# gator.net
KiCad netlist of a schematic drawn in EAGLE
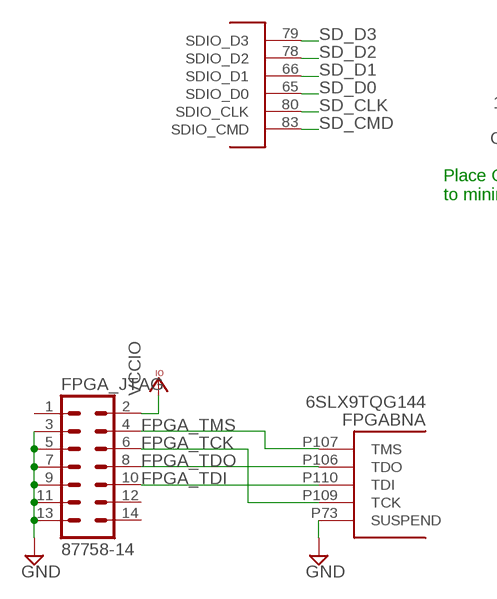
[diagram p0: schematic, sheet 1, part 1 of 2]
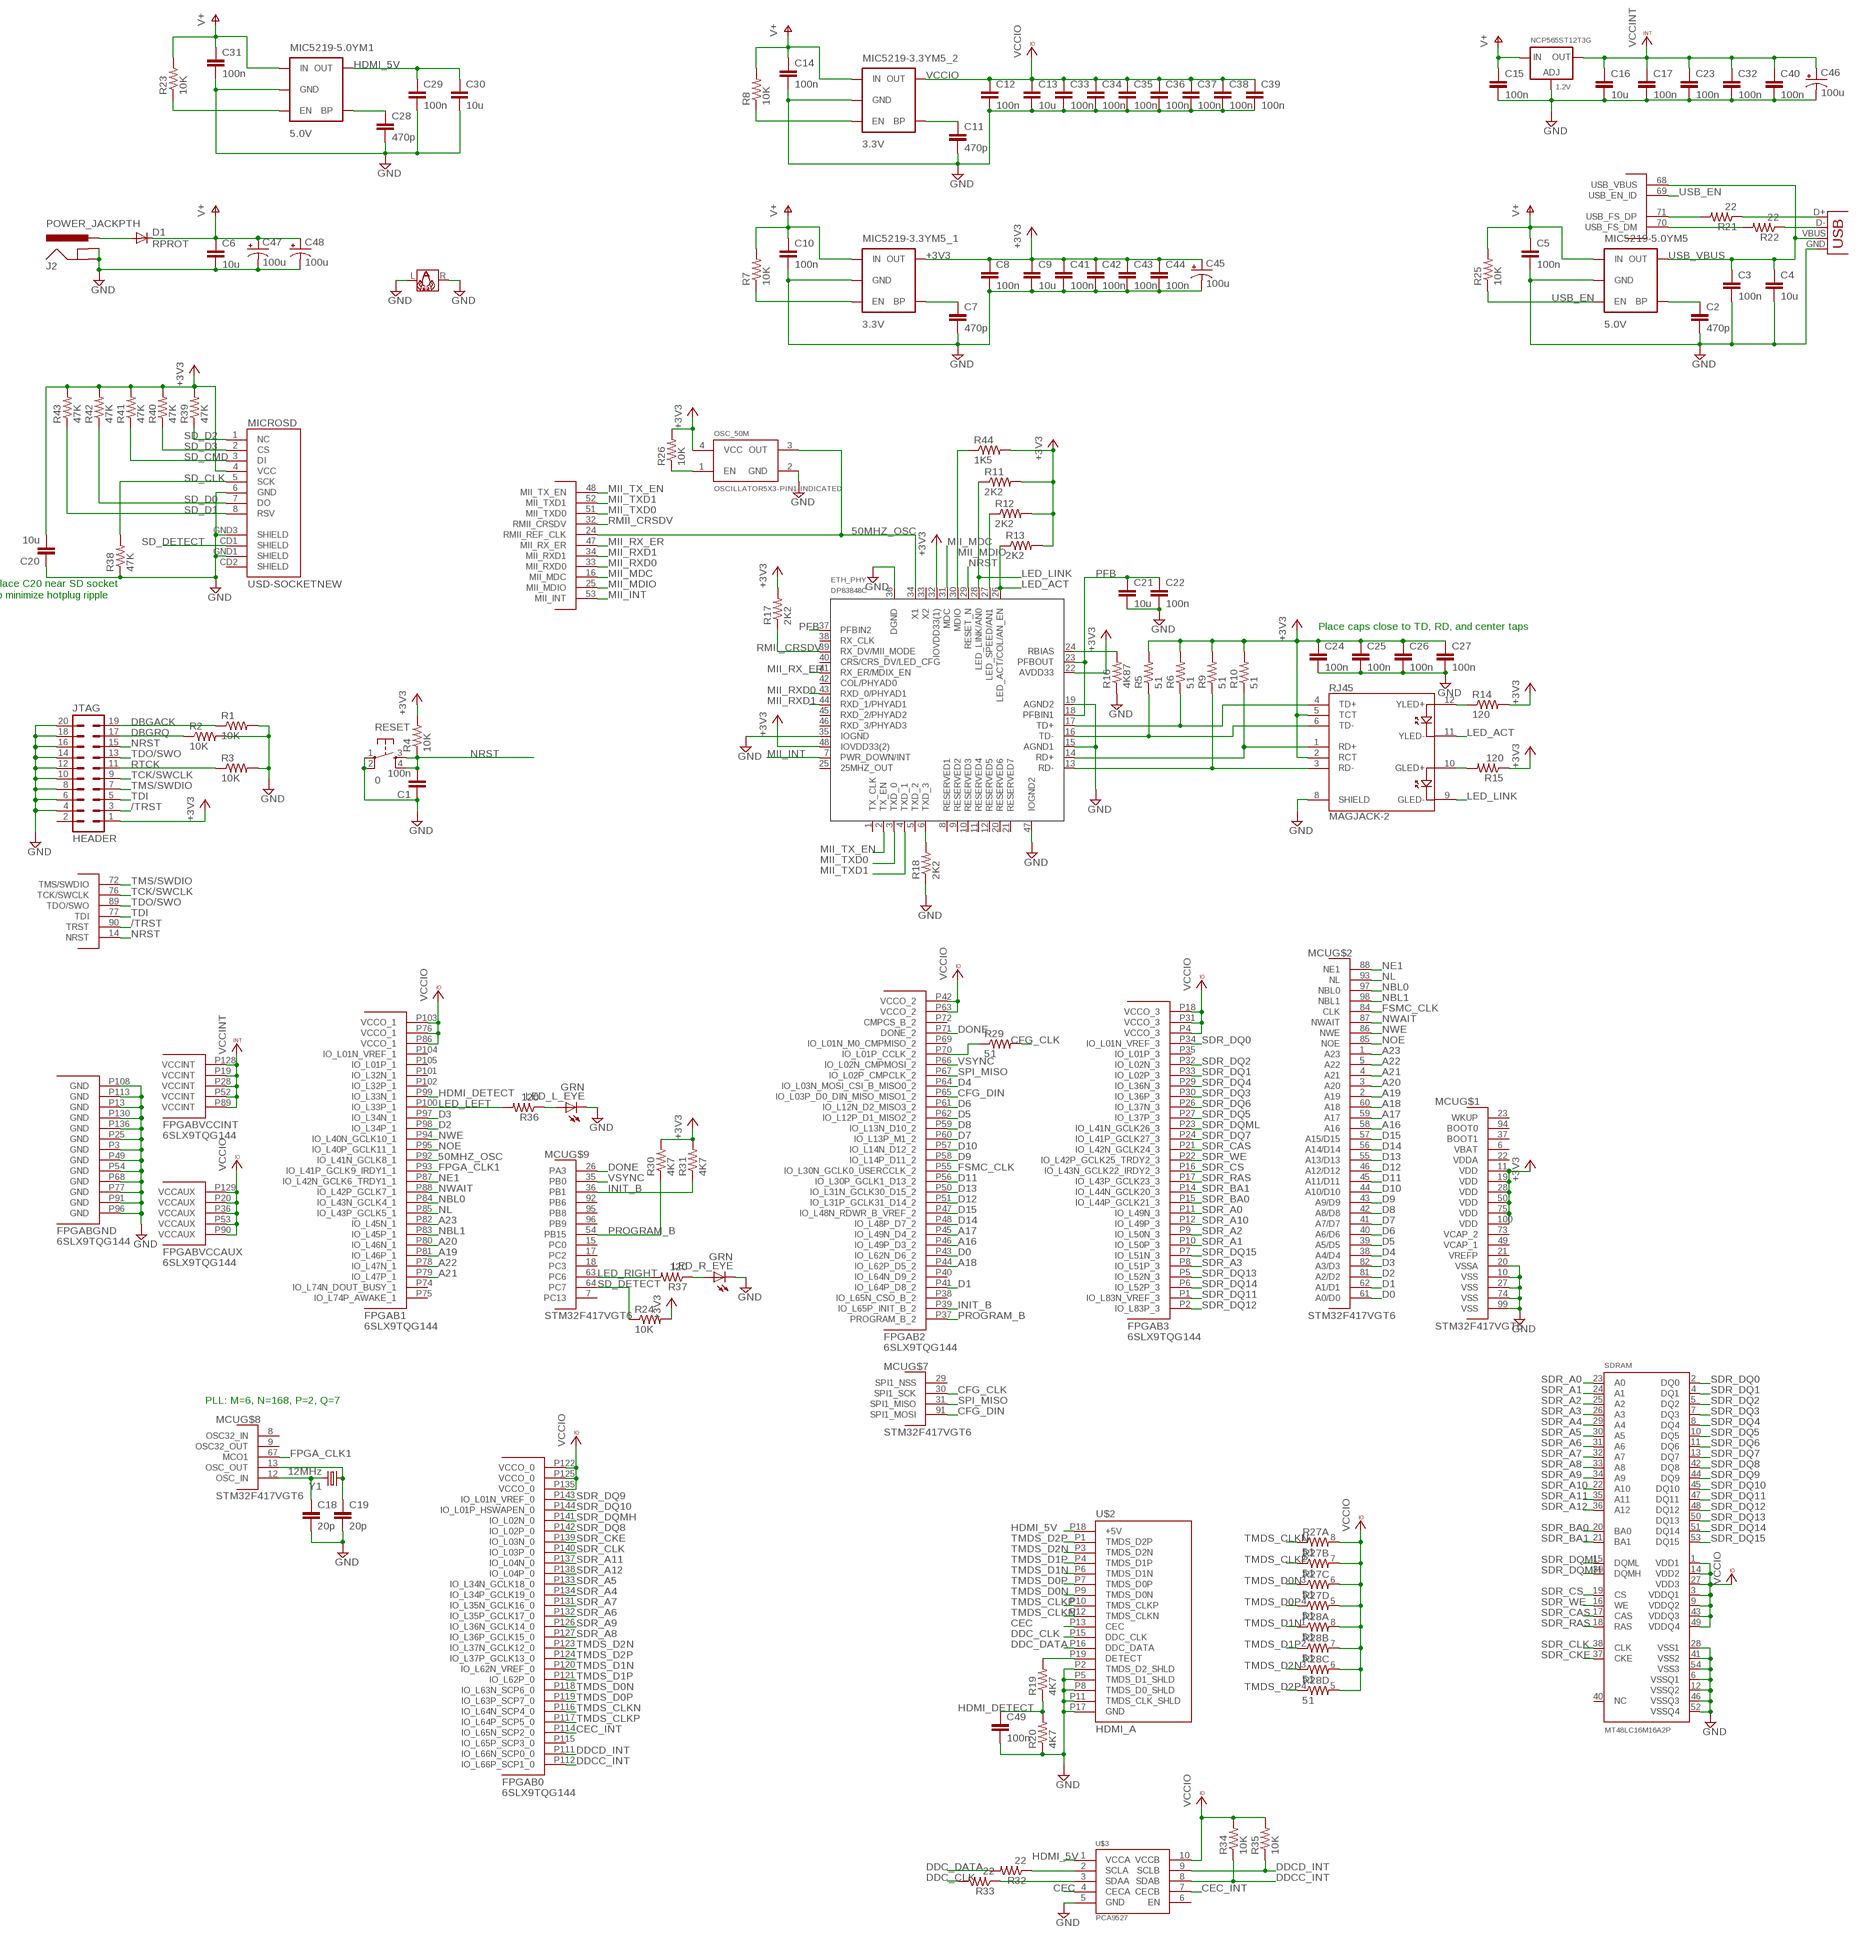
[diagram p1: schematic, sheet 1, part 2 of 2]

(export (version "E")
  (design (tool "Eeschema 10.0.6"))
  (components
    (comp (ref "C1")
      (value "100n")
      (footprint "eagle-import:0603-CAP")
      (fields (field (name "MANF") "TDK Corporation"))
      (libsource (lib "eagle-import") (part "CAP0603-CAP"))
    )
    (comp (ref "C2")
      (value "470p")
      (footprint "eagle-import:0603-CAP")
      (fields (field (name "MANF") "TDK Corporation"))
      (libsource (lib "eagle-import") (part "CAP0603-CAP"))
    )
    (comp (ref "C3")
      (value "100n")
      (footprint "eagle-import:0603-CAP")
      (fields (field (name "MANF") "TDK Corporation"))
      (libsource (lib "eagle-import") (part "CAP0603-CAP"))
    )
    (comp (ref "C4")
      (value "10u")
      (footprint "eagle-import:0603-CAP")
      (fields (field (name "MANF") "TDK Corporation"))
      (libsource (lib "eagle-import") (part "CAP0603-CAP"))
    )
    (comp (ref "C5")
      (value "100n")
      (footprint "eagle-import:0603-CAP")
      (fields (field (name "MANF") "TDK Corporation"))
      (libsource (lib "eagle-import") (part "CAP0603-CAP"))
    )
    (comp (ref "C6")
      (value "10u")
      (footprint "eagle-import:0603-CAP")
      (fields (field (name "MANF") "TDK Corporation"))
      (libsource (lib "eagle-import") (part "CAP0603-CAP"))
    )
    (comp (ref "C7")
      (value "470p")
      (footprint "eagle-import:0603-CAP")
      (fields (field (name "MANF") "TDK Corporation"))
      (libsource (lib "eagle-import") (part "CAP0603-CAP"))
    )
    (comp (ref "C8")
      (value "100n")
      (footprint "eagle-import:0603-CAP")
      (fields (field (name "MANF") "TDK Corporation"))
      (libsource (lib "eagle-import") (part "CAP0603-CAP"))
    )
    (comp (ref "C9")
      (value "10u")
      (footprint "eagle-import:0603-CAP")
      (fields (field (name "MANF") "TDK Corporation"))
      (libsource (lib "eagle-import") (part "CAP0603-CAP"))
    )
    (comp (ref "C10")
      (value "100n")
      (footprint "eagle-import:0603-CAP")
      (fields (field (name "MANF") "TDK Corporation"))
      (libsource (lib "eagle-import") (part "CAP0603-CAP"))
    )
    (comp (ref "C11")
      (value "470p")
      (footprint "eagle-import:0603-CAP")
      (fields (field (name "MANF") "TDK Corporation"))
      (libsource (lib "eagle-import") (part "CAP0603-CAP"))
    )
    (comp (ref "C12")
      (value "100n")
      (footprint "eagle-import:0603-CAP")
      (fields (field (name "MANF") "TDK Corporation"))
      (libsource (lib "eagle-import") (part "CAP0603-CAP"))
    )
    (comp (ref "C13")
      (value "10u")
      (footprint "eagle-import:0603-CAP")
      (fields (field (name "MANF") "TDK Corporation"))
      (libsource (lib "eagle-import") (part "CAP0603-CAP"))
    )
    (comp (ref "C14")
      (value "100n")
      (footprint "eagle-import:0603-CAP")
      (fields (field (name "MANF") "TDK Corporation"))
      (libsource (lib "eagle-import") (part "CAP0603-CAP"))
    )
    (comp (ref "C15")
      (value "100n")
      (footprint "eagle-import:0603-CAP")
      (fields (field (name "MANF") "TDK Corporation"))
      (libsource (lib "eagle-import") (part "CAP0603-CAP"))
    )
    (comp (ref "C16")
      (value "10u")
      (footprint "eagle-import:0603-CAP")
      (fields (field (name "MANF") "TDK Corporation"))
      (libsource (lib "eagle-import") (part "CAP0603-CAP"))
    )
    (comp (ref "C17")
      (value "100n")
      (footprint "eagle-import:0603-CAP")
      (fields (field (name "MANF") "TDK Corporation"))
      (libsource (lib "eagle-import") (part "CAP0603-CAP"))
    )
    (comp (ref "C18")
      (value "20p")
      (footprint "eagle-import:0603-CAP")
      (fields (field (name "MANF") "Murata Electronics North America"))
      (libsource (lib "eagle-import") (part "CAP0603-CAP"))
    )
    (comp (ref "C19")
      (value "20p")
      (footprint "eagle-import:0603-CAP")
      (fields (field (name "MANF") "Murata Electronics North America"))
      (libsource (lib "eagle-import") (part "CAP0603-CAP"))
    )
    (comp (ref "C20")
      (value "10u")
      (footprint "eagle-import:0603-CAP")
      (fields (field (name "MANF") "TDK Corporation"))
      (libsource (lib "eagle-import") (part "CAP0603-CAP"))
    )
    (comp (ref "C21")
      (value "10u")
      (footprint "eagle-import:0603-CAP")
      (fields (field (name "MANF") "TDK Corporation"))
      (libsource (lib "eagle-import") (part "CAP0603-CAP"))
    )
    (comp (ref "C22")
      (value "100n")
      (footprint "eagle-import:0603-CAP")
      (fields (field (name "MANF") "TDK Corporation"))
      (libsource (lib "eagle-import") (part "CAP0603-CAP"))
    )
    (comp (ref "C23")
      (value "100n")
      (footprint "eagle-import:0603-CAP")
      (fields (field (name "MANF") "TDK Corporation"))
      (libsource (lib "eagle-import") (part "CAP0603-CAP"))
    )
    (comp (ref "C24")
      (value "100n")
      (footprint "eagle-import:0603-CAP")
      (fields (field (name "MANF") "TDK Corporation"))
      (libsource (lib "eagle-import") (part "CAP0603-CAP"))
    )
    (comp (ref "C25")
      (value "100n")
      (footprint "eagle-import:0603-CAP")
      (fields (field (name "MANF") "TDK Corporation"))
      (libsource (lib "eagle-import") (part "CAP0603-CAP"))
    )
    (comp (ref "C26")
      (value "100n")
      (footprint "eagle-import:0603-CAP")
      (fields (field (name "MANF") "TDK Corporation"))
      (libsource (lib "eagle-import") (part "CAP0603-CAP"))
    )
    (comp (ref "C27")
      (value "100n")
      (footprint "eagle-import:0603-CAP")
      (fields (field (name "MANF") "TDK Corporation"))
      (libsource (lib "eagle-import") (part "CAP0603-CAP"))
    )
    (comp (ref "C28")
      (value "470p")
      (footprint "eagle-import:0603-CAP")
      (fields (field (name "MANF") "TDK Corporation"))
      (libsource (lib "eagle-import") (part "CAP0603-CAP"))
    )
    (comp (ref "C29")
      (value "100n")
      (footprint "eagle-import:0603-CAP")
      (fields (field (name "MANF") "TDK Corporation"))
      (libsource (lib "eagle-import") (part "CAP0603-CAP"))
    )
    (comp (ref "C30")
      (value "10u")
      (footprint "eagle-import:0603-CAP")
      (fields (field (name "MANF") "TDK Corporation"))
      (libsource (lib "eagle-import") (part "CAP0603-CAP"))
    )
    (comp (ref "C31")
      (value "100n")
      (footprint "eagle-import:0603-CAP")
      (fields (field (name "MANF") "TDK Corporation"))
      (libsource (lib "eagle-import") (part "CAP0603-CAP"))
    )
    (comp (ref "C32")
      (value "100n")
      (footprint "eagle-import:0603-CAP")
      (fields (field (name "MANF") "TDK Corporation"))
      (libsource (lib "eagle-import") (part "CAP0603-CAP"))
    )
    (comp (ref "C33")
      (value "100n")
      (footprint "eagle-import:0603-CAP")
      (fields (field (name "MANF") "TDK Corporation"))
      (libsource (lib "eagle-import") (part "CAP0603-CAP"))
    )
    (comp (ref "C34")
      (value "100n")
      (footprint "eagle-import:0603-CAP")
      (fields (field (name "MANF") "TDK Corporation"))
      (libsource (lib "eagle-import") (part "CAP0603-CAP"))
    )
    (comp (ref "C35")
      (value "100n")
      (footprint "eagle-import:0603-CAP")
      (fields (field (name "MANF") "TDK Corporation"))
      (libsource (lib "eagle-import") (part "CAP0603-CAP"))
    )
    (comp (ref "C36")
      (value "100n")
      (footprint "eagle-import:0603-CAP")
      (fields (field (name "MANF") "TDK Corporation"))
      (libsource (lib "eagle-import") (part "CAP0603-CAP"))
    )
    (comp (ref "C37")
      (value "100n")
      (footprint "eagle-import:0603-CAP")
      (fields (field (name "MANF") "TDK Corporation"))
      (libsource (lib "eagle-import") (part "CAP0603-CAP"))
    )
    (comp (ref "C38")
      (value "100n")
      (footprint "eagle-import:0603-CAP")
      (fields (field (name "MANF") "TDK Corporation"))
      (libsource (lib "eagle-import") (part "CAP0603-CAP"))
    )
    (comp (ref "C39")
      (value "100n")
      (footprint "eagle-import:0603-CAP")
      (fields (field (name "MANF") "TDK Corporation"))
      (libsource (lib "eagle-import") (part "CAP0603-CAP"))
    )
    (comp (ref "C40")
      (value "100n")
      (footprint "eagle-import:0603-CAP")
      (fields (field (name "MANF") "TDK Corporation"))
      (libsource (lib "eagle-import") (part "CAP0603-CAP"))
    )
    (comp (ref "C41")
      (value "100n")
      (footprint "eagle-import:0603-CAP")
      (fields (field (name "MANF") "TDK Corporation"))
      (libsource (lib "eagle-import") (part "CAP0603-CAP"))
    )
    (comp (ref "C42")
      (value "100n")
      (footprint "eagle-import:0603-CAP")
      (fields (field (name "MANF") "TDK Corporation"))
      (libsource (lib "eagle-import") (part "CAP0603-CAP"))
    )
    (comp (ref "C43")
      (value "100n")
      (footprint "eagle-import:0603-CAP")
      (fields (field (name "MANF") "TDK Corporation"))
      (libsource (lib "eagle-import") (part "CAP0603-CAP"))
    )
    (comp (ref "C44")
      (value "100n")
      (footprint "eagle-import:0603-CAP")
      (fields (field (name "MANF") "TDK Corporation"))
      (libsource (lib "eagle-import") (part "CAP0603-CAP"))
    )
    (comp (ref "C45")
      (value "100u")
      (footprint "eagle-import:CPOL-RADIAL-100UF-25V")
      (fields (field (name "MANF") "Rubycon"))
      (libsource (lib "eagle-import") (part "CAP_POLPTH1"))
    )
    (comp (ref "C46")
      (value "100u")
      (footprint "eagle-import:CPOL-RADIAL-100UF-25V")
      (fields (field (name "MANF") "Rubycon"))
      (libsource (lib "eagle-import") (part "CAP_POLPTH1"))
    )
    (comp (ref "C47")
      (value "100u")
      (footprint "eagle-import:CPOL-RADIAL-100UF-25V")
      (fields (field (name "MANF") "Rubycon"))
      (libsource (lib "eagle-import") (part "CAP_POLPTH1"))
    )
    (comp (ref "C48")
      (value "100u")
      (footprint "eagle-import:CPOL-RADIAL-100UF-25V")
      (fields (field (name "MANF") "Rubycon"))
      (libsource (lib "eagle-import") (part "CAP_POLPTH1"))
    )
    (comp (ref "C49")
      (value "100n")
      (footprint "eagle-import:0603-CAP")
      (fields (field (name "MANF") "TDK Corporation"))
      (libsource (lib "eagle-import") (part "CAP0603-CAP"))
    )
    (comp (ref "D1")
      (value "RPROT")
      (footprint "eagle-import:DIODE-1N4001")
      (fields (field (name "MANF") "STMicroelectronics"))
      (libsource (lib "eagle-import") (part "DIODEPTH"))
    )
    (comp (ref "ETH_PHY")
      (value "DP83848C")
      (footprint "eagle-import:LQFP-48")
      (fields (field (name "MANF") "Texas Instruments"))
      (libsource (lib "eagle-import") (part "DP83848C"))
    )
    (comp (ref "FPGA")
      (value "6SLX9TQG144")
      (footprint "eagle-import:TQ144")
      (fields
        (field (name "DIGIKEY#") "122-1745-ND")
        (field (name "MANF") "Xilinx Inc")
        (field (name "MANF#") "XC6SLX9-2TQG144C")
      )
      (libsource (lib "eagle-import") (part "6SLX9TQG144"))
    )
    (comp (ref "FPGA_JTAG")
      (value "87758-14")
      (footprint "eagle-import:87758-14")
      (fields (field (name "MANF") "Assmann WSW Components"))
      (libsource (lib "eagle-import") (part "87758-14"))
    )
    (comp (ref "J2")
      (value "POWER_JACKPTH")
      (footprint "eagle-import:POWER_JACK_PTH")
      (fields (field (name "MANF") "CUI Inc"))
      (libsource (lib "eagle-import") (part "POWER_JACKPTH"))
    )
    (comp (ref "JTAG")
      (value "HEADER")
      (footprint "eagle-import:ML20")
      (fields (field (name "MANF") "Sullins Connector Solutions"))
      (libsource (lib "eagle-import") (part "ML20"))
    )
    (comp (ref "LED_L_EYE")
      (value "GRN")
      (footprint "eagle-import:LED3MM")
      (fields (field (name "MANF") "Lite-On Inc"))
      (libsource (lib "eagle-import") (part "LED3MM"))
    )
    (comp (ref "LED_R_EYE")
      (value "GRN")
      (footprint "eagle-import:LED3MM")
      (fields (field (name "MANF") "Lite-On Inc"))
      (libsource (lib "eagle-import") (part "LED3MM"))
    )
    (comp (ref "MCU")
      (value "STM32F417VGT6")
      (footprint "eagle-import:LQFP-100")
      (fields
        (field (name "DIGIKEY#") "497-11900-ND")
        (field (name "MANF") "STMicroelectronics")
        (field (name "MANF#") "STM32F417VGT6")
      )
      (libsource (lib "eagle-import") (part "STM32F417VGT6"))
    )
    (comp (ref "MIC5219-3.3YM5_1")
      (value "3.3V")
      (footprint "eagle-import:SOT23-5")
      (fields (field (name "MANF") "Micrel Inc"))
      (libsource (lib "eagle-import") (part "V_REG_LDOSMD"))
    )
    (comp (ref "MIC5219-3.3YM5_2")
      (value "3.3V")
      (footprint "eagle-import:SOT23-5")
      (fields (field (name "MANF") "Micrel Inc"))
      (libsource (lib "eagle-import") (part "V_REG_LDOSMD"))
    )
    (comp (ref "MIC5219-5.0YM1")
      (value "5.0V")
      (footprint "eagle-import:SOT23-5")
      (fields (field (name "MANF") "Micrel Inc"))
      (libsource (lib "eagle-import") (part "V_REG_LDOSMD"))
    )
    (comp (ref "MIC5219-5.0YM5")
      (value "5.0V")
      (footprint "eagle-import:SOT23-5")
      (fields (field (name "MANF") "Micrel Inc"))
      (libsource (lib "eagle-import") (part "V_REG_LDOSMD"))
    )
    (comp (ref "MICROSD")
      (value "USD-SOCKETNEW")
      (footprint "eagle-import:MICRO-SD-SOCKET-PP")
      (fields (field (name "MANF") "Amphenol Commercial Products"))
      (libsource (lib "eagle-import") (part "USD-SOCKETNEW"))
    )
    (comp (ref "NCP565ST12T3G")
      (value "1.2V")
      (footprint "eagle-import:SOT223-R")
      (fields (field (name "MANF") "ON Semiconductor"))
      (libsource (lib "eagle-import") (part "LM1117SOT223-REFLOW"))
    )
    (comp (ref "OSC_50M")
      (value "OSCILLATOR5X3-PIN1-INDICATED")
      (footprint "eagle-import:CRYSTAL-OSC-SMD-5X3")
      (fields (field (name "MANF") "CTS-Frequency Controls"))
      (libsource (lib "eagle-import") (part "OSCILLATOR5X3-PIN1-INDICATED"))
    )
    (comp (ref "R1")
      (value "10K")
      (footprint "eagle-import:0603-RES")
      (fields (field (name "MANF") "Stackpole Electronics Inc"))
      (libsource (lib "eagle-import") (part "RESISTOR0603-RES"))
    )
    (comp (ref "R2")
      (value "10K")
      (footprint "eagle-import:0603-RES")
      (fields (field (name "MANF") "Stackpole Electronics Inc"))
      (libsource (lib "eagle-import") (part "RESISTOR0603-RES"))
    )
    (comp (ref "R3")
      (value "10K")
      (footprint "eagle-import:0603-RES")
      (fields (field (name "MANF") "Stackpole Electronics Inc"))
      (libsource (lib "eagle-import") (part "RESISTOR0603-RES"))
    )
    (comp (ref "R4")
      (value "10K")
      (footprint "eagle-import:0603-RES")
      (fields (field (name "MANF") "Stackpole Electronics Inc"))
      (libsource (lib "eagle-import") (part "RESISTOR0603-RES"))
    )
    (comp (ref "R5")
      (value "51")
      (footprint "eagle-import:0603-RES")
      (fields (field (name "MANF") "Stackpole Electronics Inc"))
      (libsource (lib "eagle-import") (part "RESISTOR0603-RES"))
    )
    (comp (ref "R6")
      (value "51")
      (footprint "eagle-import:0603-RES")
      (fields (field (name "MANF") "Stackpole Electronics Inc"))
      (libsource (lib "eagle-import") (part "RESISTOR0603-RES"))
    )
    (comp (ref "R7")
      (value "10K")
      (footprint "eagle-import:0603-RES")
      (fields (field (name "MANF") "Stackpole Electronics Inc"))
      (libsource (lib "eagle-import") (part "RESISTOR0603-RES"))
    )
    (comp (ref "R8")
      (value "10K")
      (footprint "eagle-import:0603-RES")
      (fields (field (name "MANF") "Stackpole Electronics Inc"))
      (libsource (lib "eagle-import") (part "RESISTOR0603-RES"))
    )
    (comp (ref "R9")
      (value "51")
      (footprint "eagle-import:0603-RES")
      (fields (field (name "MANF") "Stackpole Electronics Inc"))
      (libsource (lib "eagle-import") (part "RESISTOR0603-RES"))
    )
    (comp (ref "R10")
      (value "51")
      (footprint "eagle-import:0603-RES")
      (fields (field (name "MANF") "Stackpole Electronics Inc"))
      (libsource (lib "eagle-import") (part "RESISTOR0603-RES"))
    )
    (comp (ref "R11")
      (value "2K2")
      (footprint "eagle-import:0603-RES")
      (fields (field (name "MANF") "Stackpole Electronics Inc"))
      (libsource (lib "eagle-import") (part "RESISTOR0603-RES"))
    )
    (comp (ref "R12")
      (value "2K2")
      (footprint "eagle-import:0603-RES")
      (fields (field (name "MANF") "Stackpole Electronics Inc"))
      (libsource (lib "eagle-import") (part "RESISTOR0603-RES"))
    )
    (comp (ref "R13")
      (value "2K2")
      (footprint "eagle-import:0603-RES")
      (fields (field (name "MANF") "Stackpole Electronics Inc"))
      (libsource (lib "eagle-import") (part "RESISTOR0603-RES"))
    )
    (comp (ref "R14")
      (value "120")
      (footprint "eagle-import:0603-RES")
      (fields (field (name "MANF") "Stackpole Electronics Inc"))
      (libsource (lib "eagle-import") (part "RESISTOR0603-RES"))
    )
    (comp (ref "R15")
      (value "120")
      (footprint "eagle-import:0603-RES")
      (fields (field (name "MANF") "Stackpole Electronics Inc"))
      (libsource (lib "eagle-import") (part "RESISTOR0603-RES"))
    )
    (comp (ref "R16")
      (value "4K87")
      (footprint "eagle-import:0603-RES")
      (fields (field (name "MANF") "Stackpole Electronics Inc"))
      (libsource (lib "eagle-import") (part "RESISTOR0603-RES"))
    )
    (comp (ref "R17")
      (value "2K2")
      (footprint "eagle-import:0603-RES")
      (fields (field (name "MANF") "Stackpole Electronics Inc"))
      (libsource (lib "eagle-import") (part "RESISTOR0603-RES"))
    )
    (comp (ref "R18")
      (value "2K2")
      (footprint "eagle-import:0603-RES")
      (fields (field (name "MANF") "Stackpole Electronics Inc"))
      (libsource (lib "eagle-import") (part "RESISTOR0603-RES"))
    )
    (comp (ref "R19")
      (value "4K7")
      (footprint "eagle-import:0603-RES")
      (fields (field (name "MANF") "Stackpole Electronics Inc"))
      (libsource (lib "eagle-import") (part "RESISTOR0603-RES"))
    )
    (comp (ref "R20")
      (value "4K7")
      (footprint "eagle-import:0603-RES")
      (fields (field (name "MANF") "Stackpole Electronics Inc"))
      (libsource (lib "eagle-import") (part "RESISTOR0603-RES"))
    )
    (comp (ref "R21")
      (value "22")
      (footprint "eagle-import:0603-RES")
      (fields (field (name "MANF") "Stackpole Electronics Inc"))
      (libsource (lib "eagle-import") (part "RESISTOR0603-RES"))
    )
    (comp (ref "R22")
      (value "22")
      (footprint "eagle-import:0603-RES")
      (fields (field (name "MANF") "Stackpole Electronics Inc"))
      (libsource (lib "eagle-import") (part "RESISTOR0603-RES"))
    )
    (comp (ref "R23")
      (value "10K")
      (footprint "eagle-import:0603-RES")
      (fields (field (name "MANF") "Stackpole Electronics Inc"))
      (libsource (lib "eagle-import") (part "RESISTOR0603-RES"))
    )
    (comp (ref "R24")
      (value "10K")
      (footprint "eagle-import:0603-RES")
      (fields (field (name "MANF") "Stackpole Electronics Inc"))
      (libsource (lib "eagle-import") (part "RESISTOR0603-RES"))
    )
    (comp (ref "R25")
      (value "10K")
      (footprint "eagle-import:0603-RES")
      (fields (field (name "MANF") "Stackpole Electronics Inc"))
      (libsource (lib "eagle-import") (part "RESISTOR0603-RES"))
    )
    (comp (ref "R26")
      (value "10K")
      (footprint "eagle-import:0603-RES")
      (fields (field (name "MANF") "Stackpole Electronics Inc"))
      (libsource (lib "eagle-import") (part "RESISTOR0603-RES"))
    )
    (comp (ref "R27")
      (value "51")
      (footprint "eagle-import:0603-ARV")
      (fields
        (field (name "MANF") "Yageo")
        (field (name "DIGIKEY#") "YC164J-51CT-ND")
        (field (name "MANF#") "YC164-JR-0751RL")
      )
      (libsource (lib "eagle-import") (part "RESISTOR-ARRAY0603-ARV"))
    )
    (comp (ref "R28")
      (value "51")
      (footprint "eagle-import:0603-ARV")
      (fields
        (field (name "MANF") "Yageo")
        (field (name "DIGIKEY#") "YC164J-51CT-ND")
        (field (name "MANF#") "YC164-JR-0751RL")
      )
      (libsource (lib "eagle-import") (part "RESISTOR-ARRAY0603-ARV"))
    )
    (comp (ref "R29")
      (value "51")
      (footprint "eagle-import:0603-RES")
      (fields (field (name "MANF") "Stackpole Electronics Inc"))
      (libsource (lib "eagle-import") (part "RESISTOR0603-RES"))
    )
    (comp (ref "R30")
      (value "4K7")
      (footprint "eagle-import:0603-RES")
      (fields (field (name "MANF") "Stackpole Electronics Inc"))
      (libsource (lib "eagle-import") (part "RESISTOR0603-RES"))
    )
    (comp (ref "R31")
      (value "4K7")
      (footprint "eagle-import:0603-RES")
      (fields (field (name "MANF") "Stackpole Electronics Inc"))
      (libsource (lib "eagle-import") (part "RESISTOR0603-RES"))
    )
    (comp (ref "R32")
      (value "22")
      (footprint "eagle-import:0603-RES")
      (fields (field (name "MANF") "Stackpole Electronics Inc"))
      (libsource (lib "eagle-import") (part "RESISTOR0603-RES"))
    )
    (comp (ref "R33")
      (value "22")
      (footprint "eagle-import:0603-RES")
      (fields (field (name "MANF") "Stackpole Electronics Inc"))
      (libsource (lib "eagle-import") (part "RESISTOR0603-RES"))
    )
    (comp (ref "R34")
      (value "10K")
      (footprint "eagle-import:0603-RES")
      (fields (field (name "MANF") "Stackpole Electronics Inc"))
      (libsource (lib "eagle-import") (part "RESISTOR0603-RES"))
    )
    (comp (ref "R35")
      (value "10K")
      (footprint "eagle-import:0603-RES")
      (fields (field (name "MANF") "Stackpole Electronics Inc"))
      (libsource (lib "eagle-import") (part "RESISTOR0603-RES"))
    )
    (comp (ref "R36")
      (value "120")
      (footprint "eagle-import:0603-RES")
      (fields (field (name "MANF") "Stackpole Electronics Inc"))
      (libsource (lib "eagle-import") (part "RESISTOR0603-RES"))
    )
    (comp (ref "R37")
      (value "120")
      (footprint "eagle-import:0603-RES")
      (fields (field (name "MANF") "Stackpole Electronics Inc"))
      (libsource (lib "eagle-import") (part "RESISTOR0603-RES"))
    )
    (comp (ref "R38")
      (value "47K")
      (footprint "eagle-import:0603-RES")
      (fields (field (name "MANF") "Stackpole Electronics Inc"))
      (libsource (lib "eagle-import") (part "RESISTOR0603-RES"))
    )
    (comp (ref "R39")
      (value "47K")
      (footprint "eagle-import:0603-RES")
      (fields (field (name "MANF") "Stackpole Electronics Inc"))
      (libsource (lib "eagle-import") (part "RESISTOR0603-RES"))
    )
    (comp (ref "R40")
      (value "47K")
      (footprint "eagle-import:0603-RES")
      (fields (field (name "MANF") "Stackpole Electronics Inc"))
      (libsource (lib "eagle-import") (part "RESISTOR0603-RES"))
    )
    (comp (ref "R41")
      (value "47K")
      (footprint "eagle-import:0603-RES")
      (fields (field (name "MANF") "Stackpole Electronics Inc"))
      (libsource (lib "eagle-import") (part "RESISTOR0603-RES"))
    )
    (comp (ref "R42")
      (value "47K")
      (footprint "eagle-import:0603-RES")
      (fields (field (name "MANF") "Stackpole Electronics Inc"))
      (libsource (lib "eagle-import") (part "RESISTOR0603-RES"))
    )
    (comp (ref "R43")
      (value "47K")
      (footprint "eagle-import:0603-RES")
      (fields (field (name "MANF") "Stackpole Electronics Inc"))
      (libsource (lib "eagle-import") (part "RESISTOR0603-RES"))
    )
    (comp (ref "R44")
      (value "1K5")
      (footprint "eagle-import:0603-RES")
      (fields (field (name "MANF") "Stackpole Electronics Inc"))
      (libsource (lib "eagle-import") (part "RESISTOR0603-RES"))
    )
    (comp (ref "RESET")
      (value "0")
      (footprint "eagle-import:TACTILE-PTH")
      (fields (field (name "MANF") "TE Connectivity"))
      (libsource (lib "eagle-import") (part "TAC_SWITCHPTH"))
    )
    (comp (ref "RJ45")
      (value "MAGJACK-2")
      (footprint "eagle-import:MAGJACK-19938")
      (fields (field (name "MANF") "Stewart Connector"))
      (libsource (lib "eagle-import") (part "MAGJACK-2"))
    )
    (comp (ref "SDRAM")
      (value "MT48LC16M16A2P")
      (footprint "eagle-import:TSOP54-400")
      (fields (field (name "MANF") "Micron Technology Inc"))
      (libsource (lib "eagle-import") (part "MT48LC16M16A2P"))
    )
    (comp (ref "U$2")
      (value "HDMI_A")
      (footprint "eagle-import:HDMI_A_SMT")
      (fields (field (name "MANF") "Molex Inc"))
      (libsource (lib "eagle-import") (part "HDMI_A"))
    )
    (comp (ref "U$3")
      (value "PCA9527")
      (footprint "eagle-import:TSSOP10")
      (fields (field (name "MANF") "NXP Semiconductors"))
      (libsource (lib "eagle-import") (part "PCA9527"))
    )
    (comp (ref "U$4")
      (value "GATOR_HEAD")
      (footprint "eagle-import:GATOR_HEAD")
      (fields (field (name "MANF") "CUI Inc"))
      (libsource (lib "eagle-import") (part "GATOR_HEAD"))
    )
    (comp (ref "X1")
      (value "USB-A-S")
      (footprint "eagle-import:USB-A-S")
      (fields (field (name "MANF") "CNC Tech"))
      (libsource (lib "eagle-import") (part "USB-A-S"))
    )
    (comp (ref "Y1")
      (value "12MHz")
      (footprint "eagle-import:HC49US")
      (fields (field (name "MANF") "CTS-Frequency Controls"))
      (libsource (lib "eagle-import") (part "CRYSTALHC49US"))
    )
  )
  (nets
    (net (code "1") (name "+3V3") (class "Default")
      (node (ref "C20") (pin "2") (pinfunction "2_2") (pintype "passive"))
      (node (ref "C24") (pin "1") (pinfunction "1_1") (pintype "passive"))
      (node (ref "C25") (pin "1") (pinfunction "1_1") (pintype "passive"))
      (node (ref "C26") (pin "1") (pinfunction "1_1") (pintype "passive"))
      (node (ref "C27") (pin "1") (pinfunction "1_1") (pintype "passive"))
      (node (ref "C41") (pin "1") (pinfunction "1_1") (pintype "passive"))
      (node (ref "C42") (pin "1") (pinfunction "1_1") (pintype "passive"))
      (node (ref "C43") (pin "1") (pinfunction "1_1") (pintype "passive"))
      (node (ref "C44") (pin "1") (pinfunction "1_1") (pintype "passive"))
      (node (ref "C45") (pin "1") (pinfunction "+_1") (pintype "passive"))
      (node (ref "C8") (pin "1") (pinfunction "1_1") (pintype "passive"))
      (node (ref "C9") (pin "1") (pinfunction "1_1") (pintype "passive"))
      (node (ref "ETH_PHY") (pin "22") (pinfunction "AVDD33_22") (pintype "bidirectional"))
      (node (ref "ETH_PHY") (pin "32") (pinfunction "IOVDD33(1)_32") (pintype "bidirectional"))
      (node (ref "ETH_PHY") (pin "48") (pinfunction "IOVDD33(2)_48") (pintype "bidirectional"))
      (node (ref "JTAG") (pin "1") (pinfunction "1_1") (pintype "passive"))
      (node (ref "MCU") (pin "100") (pinfunction "VDD_100") (pintype "bidirectional"))
      (node (ref "MCU") (pin "11") (pinfunction "VDD_11") (pintype "bidirectional"))
      (node (ref "MCU") (pin "19") (pinfunction "VDD_19") (pintype "bidirectional"))
      (node (ref "MCU") (pin "28") (pinfunction "VDD_28") (pintype "bidirectional"))
      (node (ref "MCU") (pin "50") (pinfunction "VDD_50") (pintype "bidirectional"))
      (node (ref "MCU") (pin "75") (pinfunction "VDD_75") (pintype "bidirectional"))
      (node (ref "MIC5219-3.3YM5_1") (pin "5") (pinfunction "OUT_5") (pintype "passive"))
      (node (ref "MICROSD") (pin "4") (pinfunction "VCC_4") (pintype "bidirectional"))
      (node (ref "OSC_50M") (pin "4") (pinfunction "VCC_4") (pintype "bidirectional"))
      (node (ref "R10") (pin "2") (pinfunction "2_2") (pintype "passive"))
      (node (ref "R11") (pin "2") (pinfunction "2_2") (pintype "passive"))
      (node (ref "R12") (pin "2") (pinfunction "2_2") (pintype "passive"))
      (node (ref "R13") (pin "2") (pinfunction "2_2") (pintype "passive"))
      (node (ref "R14") (pin "2") (pinfunction "2_2") (pintype "passive"))
      (node (ref "R15") (pin "1") (pinfunction "1_1") (pintype "passive"))
      (node (ref "R17") (pin "2") (pinfunction "2_2") (pintype "passive"))
      (node (ref "R24") (pin "2") (pinfunction "2_2") (pintype "passive"))
      (node (ref "R26") (pin "2") (pinfunction "2_2") (pintype "passive"))
      (node (ref "R30") (pin "2") (pinfunction "2_2") (pintype "passive"))
      (node (ref "R31") (pin "2") (pinfunction "2_2") (pintype "passive"))
      (node (ref "R39") (pin "2") (pinfunction "2_2") (pintype "passive"))
      (node (ref "R4") (pin "2") (pinfunction "2_2") (pintype "passive"))
      (node (ref "R40") (pin "2") (pinfunction "2_2") (pintype "passive"))
      (node (ref "R41") (pin "2") (pinfunction "2_2") (pintype "passive"))
      (node (ref "R42") (pin "2") (pinfunction "2_2") (pintype "passive"))
      (node (ref "R43") (pin "2") (pinfunction "2_2") (pintype "passive"))
      (node (ref "R44") (pin "2") (pinfunction "2_2") (pintype "passive"))
      (node (ref "R5") (pin "2") (pinfunction "2_2") (pintype "passive"))
      (node (ref "R6") (pin "2") (pinfunction "2_2") (pintype "passive"))
      (node (ref "R9") (pin "2") (pinfunction "2_2") (pintype "passive"))
      (node (ref "RJ45") (pin "2") (pinfunction "RCT_2") (pintype "bidirectional"))
      (node (ref "RJ45") (pin "5") (pinfunction "TCT_5") (pintype "bidirectional"))
    )
    (net (code "2") (name "/50MHZ_OSC") (class "Default")
      (node (ref "ETH_PHY") (pin "34") (pinfunction "X1_34") (pintype "bidirectional"))
      (node (ref "FPGA") (pin "P92") (pinfunction "IO_L41N_GCLK8_1_P92") (pintype "bidirectional"))
      (node (ref "MCU") (pin "24") (pinfunction "RMII_REF_CLK_24") (pintype "bidirectional"))
      (node (ref "OSC_50M") (pin "3") (pinfunction "OUT_3") (pintype "bidirectional"))
    )
    (net (code "3") (name "/A16") (class "Default")
      (node (ref "FPGA") (pin "P46") (pinfunction "IO_L49P_D3_2_P46") (pintype "bidirectional"))
      (node (ref "MCU") (pin "58") (pinfunction "A16_58") (pintype "bidirectional"))
    )
    (net (code "4") (name "/A17") (class "Default")
      (node (ref "FPGA") (pin "P45") (pinfunction "IO_L49N_D4_2_P45") (pintype "bidirectional"))
      (node (ref "MCU") (pin "59") (pinfunction "A17_59") (pintype "bidirectional"))
    )
    (net (code "5") (name "/A18") (class "Default")
      (node (ref "FPGA") (pin "P44") (pinfunction "IO_L62P_D5_2_P44") (pintype "bidirectional"))
      (node (ref "MCU") (pin "60") (pinfunction "A18_60") (pintype "bidirectional"))
    )
    (net (code "6") (name "/A19") (class "Default")
      (node (ref "FPGA") (pin "P81") (pinfunction "IO_L46P_1_P81") (pintype "bidirectional"))
      (node (ref "MCU") (pin "2") (pinfunction "A19_2") (pintype "bidirectional"))
    )
    (net (code "7") (name "/A20") (class "Default")
      (node (ref "FPGA") (pin "P80") (pinfunction "IO_L46N_1_P80") (pintype "bidirectional"))
      (node (ref "MCU") (pin "3") (pinfunction "A20_3") (pintype "bidirectional"))
    )
    (net (code "8") (name "/A21") (class "Default")
      (node (ref "FPGA") (pin "P79") (pinfunction "IO_L47P_1_P79") (pintype "bidirectional"))
      (node (ref "MCU") (pin "4") (pinfunction "A21_4") (pintype "bidirectional"))
    )
    (net (code "9") (name "/A22") (class "Default")
      (node (ref "FPGA") (pin "P78") (pinfunction "IO_L47N_1_P78") (pintype "bidirectional"))
      (node (ref "MCU") (pin "5") (pinfunction "A22_5") (pintype "bidirectional"))
    )
    (net (code "10") (name "/A23") (class "Default")
      (node (ref "FPGA") (pin "P82") (pinfunction "IO_L45N_1_P82") (pintype "bidirectional"))
      (node (ref "MCU") (pin "1") (pinfunction "A23_1") (pintype "bidirectional"))
    )
    (net (code "11") (name "/CEC") (class "Default")
      (node (ref "U$2") (pin "P13") (pinfunction "CEC_P13") (pintype "bidirectional"))
      (node (ref "U$3") (pin "4") (pinfunction "CECA_4") (pintype "bidirectional"))
    )
    (net (code "12") (name "/CEC_INT") (class "Default")
      (node (ref "FPGA") (pin "P114") (pinfunction "IO_L65N_SCP2_0_P114") (pintype "bidirectional"))
      (node (ref "U$3") (pin "7") (pinfunction "CECB_7") (pintype "bidirectional"))
    )
    (net (code "13") (name "/CFG_CLK") (class "Default")
      (node (ref "MCU") (pin "30") (pinfunction "SPI1_SCK_30") (pintype "bidirectional"))
      (node (ref "R29") (pin "2") (pinfunction "2_2") (pintype "passive"))
    )
    (net (code "14") (name "/CFG_DIN") (class "Default")
      (node (ref "FPGA") (pin "P65") (pinfunction "IO_L03P_D0_DIN_MISO_MISO1_2_P65") (pintype "bidirectional"))
      (node (ref "MCU") (pin "91") (pinfunction "SPI1_MOSI_91") (pintype "bidirectional"))
    )
    (net (code "15") (name "/D0") (class "Default")
      (node (ref "FPGA") (pin "P43") (pinfunction "IO_L62N_D6_2_P43") (pintype "bidirectional"))
      (node (ref "MCU") (pin "61") (pinfunction "A0/D0_61") (pintype "bidirectional"))
    )
    (net (code "16") (name "/D1") (class "Default")
      (node (ref "FPGA") (pin "P41") (pinfunction "IO_L64P_D8_2_P41") (pintype "bidirectional"))
      (node (ref "MCU") (pin "62") (pinfunction "A1/D1_62") (pintype "bidirectional"))
    )
    (net (code "17") (name "/D2") (class "Default")
      (node (ref "FPGA") (pin "P98") (pinfunction "IO_L34P_1_P98") (pintype "bidirectional"))
      (node (ref "MCU") (pin "81") (pinfunction "A2/D2_81") (pintype "bidirectional"))
    )
    (net (code "18") (name "/D3") (class "Default")
      (node (ref "FPGA") (pin "P97") (pinfunction "IO_L34N_1_P97") (pintype "bidirectional"))
      (node (ref "MCU") (pin "82") (pinfunction "A3/D3_82") (pintype "bidirectional"))
    )
    (net (code "19") (name "/D4") (class "Default")
      (node (ref "FPGA") (pin "P64") (pinfunction "IO_L03N_MOSI_CSI_B_MISO0_2_P64") (pintype "bidirectional"))
      (node (ref "MCU") (pin "38") (pinfunction "A4/D4_38") (pintype "bidirectional"))
    )
    (net (code "20") (name "/D5") (class "Default")
      (node (ref "FPGA") (pin "P62") (pinfunction "IO_L12P_D1_MISO2_2_P62") (pintype "bidirectional"))
      (node (ref "MCU") (pin "39") (pinfunction "A5/D5_39") (pintype "bidirectional"))
    )
    (net (code "21") (name "/D6") (class "Default")
      (node (ref "FPGA") (pin "P61") (pinfunction "IO_L12N_D2_MISO3_2_P61") (pintype "bidirectional"))
      (node (ref "MCU") (pin "40") (pinfunction "A6/D6_40") (pintype "bidirectional"))
    )
    (net (code "22") (name "/D7") (class "Default")
      (node (ref "FPGA") (pin "P60") (pinfunction "IO_L13P_M1_2_P60") (pintype "bidirectional"))
      (node (ref "MCU") (pin "41") (pinfunction "A7/D7_41") (pintype "bidirectional"))
    )
    (net (code "23") (name "/D8") (class "Default")
      (node (ref "FPGA") (pin "P59") (pinfunction "IO_L13N_D10_2_P59") (pintype "bidirectional"))
      (node (ref "MCU") (pin "42") (pinfunction "A8/D8_42") (pintype "bidirectional"))
    )
    (net (code "24") (name "/D9") (class "Default")
      (node (ref "FPGA") (pin "P58") (pinfunction "IO_L14P_D11_2_P58") (pintype "bidirectional"))
      (node (ref "MCU") (pin "43") (pinfunction "A9/D9_43") (pintype "bidirectional"))
    )
    (net (code "25") (name "/D10") (class "Default")
      (node (ref "FPGA") (pin "P57") (pinfunction "IO_L14N_D12_2_P57") (pintype "bidirectional"))
      (node (ref "MCU") (pin "44") (pinfunction "A10/D10_44") (pintype "bidirectional"))
    )
    (net (code "26") (name "/D11") (class "Default")
      (node (ref "FPGA") (pin "P56") (pinfunction "IO_L30P_GCLK1_D13_2_P56") (pintype "bidirectional"))
      (node (ref "MCU") (pin "45") (pinfunction "A11/D11_45") (pintype "bidirectional"))
    )
    (net (code "27") (name "/D12") (class "Default")
      (node (ref "FPGA") (pin "P51") (pinfunction "IO_L31P_GCLK31_D14_2_P51") (pintype "bidirectional"))
      (node (ref "MCU") (pin "46") (pinfunction "A12/D12_46") (pintype "bidirectional"))
    )
    (net (code "28") (name "/D13") (class "Default")
      (node (ref "FPGA") (pin "P50") (pinfunction "IO_L31N_GCLK30_D15_2_P50") (pintype "bidirectional"))
      (node (ref "MCU") (pin "55") (pinfunction "A13/D13_55") (pintype "bidirectional"))
    )
    (net (code "29") (name "/D14") (class "Default")
      (node (ref "FPGA") (pin "P48") (pinfunction "IO_L48P_D7_2_P48") (pintype "bidirectional"))
      (node (ref "MCU") (pin "56") (pinfunction "A14/D14_56") (pintype "bidirectional"))
    )
    (net (code "30") (name "/D15") (class "Default")
      (node (ref "FPGA") (pin "P47") (pinfunction "IO_L48N_RDWR_B_VREF_2_P47") (pintype "bidirectional"))
      (node (ref "MCU") (pin "57") (pinfunction "A15/D15_57") (pintype "bidirectional"))
    )
    (net (code "31") (name "/DBGACK") (class "Default")
      (node (ref "JTAG") (pin "19") (pinfunction "19_19") (pintype "passive"))
      (node (ref "R1") (pin "1") (pinfunction "1_1") (pintype "passive"))
    )
    (net (code "32") (name "/DBGRQ") (class "Default")
      (node (ref "JTAG") (pin "17") (pinfunction "17_17") (pintype "passive"))
      (node (ref "R2") (pin "1") (pinfunction "1_1") (pintype "passive"))
    )
    (net (code "33") (name "/DDCC_INT") (class "Default")
      (node (ref "FPGA") (pin "P112") (pinfunction "IO_L66P_SCP1_0_P112") (pintype "bidirectional"))
      (node (ref "R34") (pin "1") (pinfunction "1_1") (pintype "passive"))
      (node (ref "U$3") (pin "8") (pinfunction "SDAB_8") (pintype "bidirectional"))
    )
    (net (code "34") (name "/DDCD_INT") (class "Default")
      (node (ref "FPGA") (pin "P111") (pinfunction "IO_L66N_SCP0_0_P111") (pintype "bidirectional"))
      (node (ref "R35") (pin "1") (pinfunction "1_1") (pintype "passive"))
      (node (ref "U$3") (pin "9") (pinfunction "SCLB_9") (pintype "bidirectional"))
    )
    (net (code "35") (name "/DDC_CLK") (class "Default")
      (node (ref "R33") (pin "2") (pinfunction "2_2") (pintype "passive"))
      (node (ref "U$2") (pin "P15") (pinfunction "DDC_CLK_P15") (pintype "bidirectional"))
    )
    (net (code "36") (name "/DDC_DATA") (class "Default")
      (node (ref "R32") (pin "2") (pinfunction "2_2") (pintype "passive"))
      (node (ref "U$2") (pin "P16") (pinfunction "DDC_DATA_P16") (pintype "bidirectional"))
    )
    (net (code "37") (name "/DONE") (class "Default")
      (node (ref "FPGA") (pin "P71") (pinfunction "DONE_2_P71") (pintype "bidirectional"))
      (node (ref "MCU") (pin "26") (pinfunction "PA3_26") (pintype "bidirectional"))
    )
    (net (code "38") (name "/FPGA_CLK1") (class "Default")
      (node (ref "FPGA") (pin "P93") (pinfunction "IO_L41P_GCLK9_IRDY1_1_P93") (pintype "bidirectional"))
      (node (ref "MCU") (pin "67") (pinfunction "MCO1_67") (pintype "bidirectional"))
    )
    (net (code "39") (name "/FPGA_TCK") (class "Default")
      (node (ref "FPGA") (pin "P109") (pinfunction "TCK_P109") (pintype "input"))
      (node (ref "FPGA_JTAG") (pin "6") (pinfunction "6_6") (pintype "passive"))
    )
    (net (code "40") (name "/FPGA_TDI") (class "Default")
      (node (ref "FPGA") (pin "P110") (pinfunction "TDI_P110") (pintype "input"))
      (node (ref "FPGA_JTAG") (pin "10") (pinfunction "10_10") (pintype "passive"))
    )
    (net (code "41") (name "/FPGA_TDO") (class "Default")
      (node (ref "FPGA") (pin "P106") (pinfunction "TDO_P106") (pintype "output"))
      (node (ref "FPGA_JTAG") (pin "8") (pinfunction "8_8") (pintype "passive"))
    )
    (net (code "42") (name "/FPGA_TMS") (class "Default")
      (node (ref "FPGA") (pin "P107") (pinfunction "TMS_P107") (pintype "input"))
      (node (ref "FPGA_JTAG") (pin "4") (pinfunction "4_4") (pintype "passive"))
    )
    (net (code "43") (name "/FSMC_CLK") (class "Default")
      (node (ref "FPGA") (pin "P55") (pinfunction "IO_L30N_GCLK0_USERCCLK_2_P55") (pintype "bidirectional"))
      (node (ref "MCU") (pin "84") (pinfunction "CLK_84") (pintype "bidirectional"))
    )
    (net (code "44") (name "/HDMI_5V") (class "Default")
      (node (ref "C29") (pin "1") (pinfunction "1_1") (pintype "passive"))
      (node (ref "C30") (pin "1") (pinfunction "1_1") (pintype "passive"))
      (node (ref "MIC5219-5.0YM1") (pin "5") (pinfunction "OUT_5") (pintype "passive"))
      (node (ref "U$2") (pin "P18") (pinfunction "+5V_P18") (pintype "bidirectional"))
      (node (ref "U$3") (pin "1") (pinfunction "VCCA_1") (pintype "bidirectional"))
    )
    (net (code "45") (name "/HDMI_DETECT") (class "Default")
      (node (ref "C49") (pin "1") (pinfunction "1_1") (pintype "passive"))
      (node (ref "FPGA") (pin "P99") (pinfunction "IO_L33N_1_P99") (pintype "bidirectional"))
      (node (ref "R19") (pin "1") (pinfunction "1_1") (pintype "passive"))
      (node (ref "R20") (pin "2") (pinfunction "2_2") (pintype "passive"))
    )
    (net (code "46") (name "/INIT_B") (class "Default")
      (node (ref "FPGA") (pin "P39") (pinfunction "IO_L65P_INIT_B_2_P39") (pintype "bidirectional"))
      (node (ref "MCU") (pin "36") (pinfunction "PB1_36") (pintype "bidirectional"))
      (node (ref "R31") (pin "1") (pinfunction "1_1") (pintype "passive"))
    )
    (net (code "47") (name "/LED_ACT") (class "Default")
      (node (ref "ETH_PHY") (pin "26") (pinfunction "LED_ACT/COL/AN_EN_26") (pintype "bidirectional"))
      (node (ref "R13") (pin "1") (pinfunction "1_1") (pintype "passive"))
      (node (ref "RJ45") (pin "11") (pinfunction "YLED-_11") (pintype "bidirectional"))
    )
    (net (code "48") (name "/LED_LEFT") (class "Default")
      (node (ref "FPGA") (pin "P100") (pinfunction "IO_L33P_1_P100") (pintype "bidirectional"))
      (node (ref "R36") (pin "2") (pinfunction "2_2") (pintype "passive"))
    )
    (net (code "49") (name "/LED_LINK") (class "Default")
      (node (ref "ETH_PHY") (pin "28") (pinfunction "LED_LINK/AN0_28") (pintype "bidirectional"))
      (node (ref "R11") (pin "1") (pinfunction "1_1") (pintype "passive"))
      (node (ref "RJ45") (pin "9") (pinfunction "GLED-_9") (pintype "bidirectional"))
    )
    (net (code "50") (name "/LED_RIGHT") (class "Default")
      (node (ref "MCU") (pin "63") (pinfunction "PC6_63") (pintype "bidirectional"))
      (node (ref "R37") (pin "2") (pinfunction "2_2") (pintype "passive"))
    )
    (net (code "51") (name "/MII_INT") (class "Default")
      (node (ref "ETH_PHY") (pin "7") (pinfunction "PWR_DOWN/INT_7") (pintype "bidirectional"))
      (node (ref "MCU") (pin "53") (pinfunction "MII_INT_53") (pintype "bidirectional"))
    )
    (net (code "52") (name "/MII_MDC") (class "Default")
      (node (ref "ETH_PHY") (pin "31") (pinfunction "MDC_31") (pintype "bidirectional"))
      (node (ref "MCU") (pin "16") (pinfunction "MII_MDC_16") (pintype "bidirectional"))
    )
    (net (code "53") (name "/MII_MDIO") (class "Default")
      (node (ref "ETH_PHY") (pin "30") (pinfunction "MDIO_30") (pintype "bidirectional"))
      (node (ref "MCU") (pin "25") (pinfunction "MII_MDIO_25") (pintype "bidirectional"))
      (node (ref "R44") (pin "1") (pinfunction "1_1") (pintype "passive"))
    )
    (net (code "54") (name "/MII_RXD0") (class "Default")
      (node (ref "ETH_PHY") (pin "43") (pinfunction "RXD_0/PHYAD1_43") (pintype "bidirectional"))
      (node (ref "MCU") (pin "33") (pinfunction "MII_RXD0_33") (pintype "bidirectional"))
    )
    (net (code "55") (name "/MII_RXD1") (class "Default")
      (node (ref "ETH_PHY") (pin "44") (pinfunction "RXD_1/PHYAD1_44") (pintype "bidirectional"))
      (node (ref "MCU") (pin "34") (pinfunction "MII_RXD1_34") (pintype "bidirectional"))
    )
    (net (code "56") (name "/MII_RX_ER") (class "Default")
      (node (ref "ETH_PHY") (pin "41") (pinfunction "RX_ER/MDIX_EN_41") (pintype "bidirectional"))
      (node (ref "MCU") (pin "47") (pinfunction "MII_RX_ER_47") (pintype "bidirectional"))
    )
    (net (code "57") (name "/MII_TXD0") (class "Default")
      (node (ref "ETH_PHY") (pin "3") (pinfunction "TXD_0_3") (pintype "bidirectional"))
      (node (ref "MCU") (pin "51") (pinfunction "MII_TXD0_51") (pintype "bidirectional"))
    )
    (net (code "58") (name "/MII_TXD1") (class "Default")
      (node (ref "ETH_PHY") (pin "4") (pinfunction "TXD_1_4") (pintype "bidirectional"))
      (node (ref "MCU") (pin "52") (pinfunction "MII_TXD1_52") (pintype "bidirectional"))
    )
    (net (code "59") (name "/MII_TX_EN") (class "Default")
      (node (ref "ETH_PHY") (pin "2") (pinfunction "TX_EN_2") (pintype "bidirectional"))
      (node (ref "MCU") (pin "48") (pinfunction "MII_TX_EN_48") (pintype "bidirectional"))
    )
    (net (code "60") (name "/NBL0") (class "Default")
      (node (ref "FPGA") (pin "P84") (pinfunction "IO_L43N_GCLK4_1_P84") (pintype "bidirectional"))
      (node (ref "MCU") (pin "97") (pinfunction "NBL0_97") (pintype "bidirectional"))
    )
    (net (code "61") (name "/NBL1") (class "Default")
      (node (ref "FPGA") (pin "P83") (pinfunction "IO_L45P_1_P83") (pintype "bidirectional"))
      (node (ref "MCU") (pin "98") (pinfunction "NBL1_98") (pintype "bidirectional"))
    )
    (net (code "62") (name "/NE1") (class "Default")
      (node (ref "FPGA") (pin "P87") (pinfunction "IO_L42N_GCLK6_TRDY1_1_P87") (pintype "bidirectional"))
      (node (ref "MCU") (pin "88") (pinfunction "NE1_88") (pintype "bidirectional"))
    )
    (net (code "63") (name "/NL") (class "Default")
      (node (ref "FPGA") (pin "P85") (pinfunction "IO_L43P_GCLK5_1_P85") (pintype "bidirectional"))
      (node (ref "MCU") (pin "93") (pinfunction "NL_93") (pintype "bidirectional"))
    )
    (net (code "64") (name "/NOE") (class "Default")
      (node (ref "FPGA") (pin "P95") (pinfunction "IO_L40P_GCLK11_1_P95") (pintype "bidirectional"))
      (node (ref "MCU") (pin "85") (pinfunction "NOE_85") (pintype "bidirectional"))
    )
    (net (code "65") (name "/NRST") (class "Default")
      (node (ref "C1") (pin "2") (pinfunction "2_2") (pintype "passive"))
      (node (ref "ETH_PHY") (pin "29") (pinfunction "RESET_N_29") (pintype "bidirectional"))
      (node (ref "JTAG") (pin "15") (pinfunction "15_15") (pintype "passive"))
      (node (ref "MCU") (pin "14") (pinfunction "NRST_14") (pintype "bidirectional"))
      (node (ref "R4") (pin "1") (pinfunction "1_1") (pintype "passive"))
      (node (ref "RESET") (pin "3") (pinfunction "3_3") (pintype "passive"))
      (node (ref "RESET") (pin "4") (pinfunction "4_4") (pintype "passive"))
    )
    (net (code "66") (name "/NWAIT") (class "Default")
      (node (ref "FPGA") (pin "P88") (pinfunction "IO_L42P_GCLK7_1_P88") (pintype "bidirectional"))
      (node (ref "MCU") (pin "87") (pinfunction "NWAIT_87") (pintype "bidirectional"))
    )
    (net (code "67") (name "/NWE") (class "Default")
      (node (ref "FPGA") (pin "P94") (pinfunction "IO_L40N_GCLK10_1_P94") (pintype "bidirectional"))
      (node (ref "MCU") (pin "86") (pinfunction "NWE_86") (pintype "bidirectional"))
    )
    (net (code "68") (name "/PFB") (class "Default")
      (node (ref "C21") (pin "1") (pinfunction "1_1") (pintype "passive"))
      (node (ref "C22") (pin "1") (pinfunction "1_1") (pintype "passive"))
      (node (ref "ETH_PHY") (pin "18") (pinfunction "PFBIN1_18") (pintype "bidirectional"))
      (node (ref "ETH_PHY") (pin "23") (pinfunction "PFBOUT_23") (pintype "bidirectional"))
      (node (ref "ETH_PHY") (pin "37") (pinfunction "PFBIN2_37") (pintype "bidirectional"))
    )
    (net (code "69") (name "/PROGRAM_B") (class "Default")
      (node (ref "FPGA") (pin "P37") (pinfunction "PROGRAM_B_2_P37") (pintype "input"))
      (node (ref "MCU") (pin "54") (pinfunction "PB15_54") (pintype "bidirectional"))
      (node (ref "R30") (pin "1") (pinfunction "1_1") (pintype "passive"))
    )
    (net (code "70") (name "/RMII_CRSDV") (class "Default")
      (node (ref "ETH_PHY") (pin "39") (pinfunction "RX_DV/MII_MODE_39") (pintype "bidirectional"))
      (node (ref "MCU") (pin "32") (pinfunction "RMII_CRSDV_32") (pintype "bidirectional"))
      (node (ref "R17") (pin "1") (pinfunction "1_1") (pintype "passive"))
    )
    (net (code "71") (name "/RTCK") (class "Default")
      (node (ref "JTAG") (pin "11") (pinfunction "11_11") (pintype "passive"))
      (node (ref "R3") (pin "1") (pinfunction "1_1") (pintype "passive"))
    )
    (net (code "72") (name "/SDR_A0") (class "Default")
      (node (ref "FPGA") (pin "P11") (pinfunction "IO_L49N_3_P11") (pintype "bidirectional"))
      (node (ref "SDRAM") (pin "23") (pinfunction "A0_23") (pintype "bidirectional"))
    )
    (net (code "73") (name "/SDR_A1") (class "Default")
      (node (ref "FPGA") (pin "P10") (pinfunction "IO_L50P_3_P10") (pintype "bidirectional"))
      (node (ref "SDRAM") (pin "24") (pinfunction "A1_24") (pintype "bidirectional"))
    )
    (net (code "74") (name "/SDR_A2") (class "Default")
      (node (ref "FPGA") (pin "P9") (pinfunction "IO_L50N_3_P9") (pintype "bidirectional"))
      (node (ref "SDRAM") (pin "25") (pinfunction "A2_25") (pintype "bidirectional"))
    )
    (net (code "75") (name "/SDR_A3") (class "Default")
      (node (ref "FPGA") (pin "P8") (pinfunction "IO_L51P_3_P8") (pintype "bidirectional"))
      (node (ref "SDRAM") (pin "26") (pinfunction "A3_26") (pintype "bidirectional"))
    )
    (net (code "76") (name "/SDR_A4") (class "Default")
      (node (ref "FPGA") (pin "P134") (pinfunction "IO_L34P_GCLK19_0_P134") (pintype "bidirectional"))
      (node (ref "SDRAM") (pin "29") (pinfunction "A4_29") (pintype "bidirectional"))
    )
    (net (code "77") (name "/SDR_A5") (class "Default")
      (node (ref "FPGA") (pin "P133") (pinfunction "IO_L34N_GCLK18_0_P133") (pintype "bidirectional"))
      (node (ref "SDRAM") (pin "30") (pinfunction "A5_30") (pintype "bidirectional"))
    )
    (net (code "78") (name "/SDR_A6") (class "Default")
      (node (ref "FPGA") (pin "P132") (pinfunction "IO_L35P_GCLK17_0_P132") (pintype "bidirectional"))
      (node (ref "SDRAM") (pin "31") (pinfunction "A6_31") (pintype "bidirectional"))
    )
    (net (code "79") (name "/SDR_A7") (class "Default")
      (node (ref "FPGA") (pin "P131") (pinfunction "IO_L35N_GCLK16_0_P131") (pintype "bidirectional"))
      (node (ref "SDRAM") (pin "32") (pinfunction "A7_32") (pintype "bidirectional"))
    )
    (net (code "80") (name "/SDR_A8") (class "Default")
      (node (ref "FPGA") (pin "P127") (pinfunction "IO_L36P_GCLK15_0_P127") (pintype "bidirectional"))
      (node (ref "SDRAM") (pin "33") (pinfunction "A8_33") (pintype "bidirectional"))
    )
    (net (code "81") (name "/SDR_A9") (class "Default")
      (node (ref "FPGA") (pin "P126") (pinfunction "IO_L36N_GCLK14_0_P126") (pintype "bidirectional"))
      (node (ref "SDRAM") (pin "34") (pinfunction "A9_34") (pintype "bidirectional"))
    )
    (net (code "82") (name "/SDR_A10") (class "Default")
      (node (ref "FPGA") (pin "P12") (pinfunction "IO_L49P_3_P12") (pintype "bidirectional"))
      (node (ref "SDRAM") (pin "22") (pinfunction "A10_22") (pintype "bidirectional"))
    )
    (net (code "83") (name "/SDR_A11") (class "Default")
      (node (ref "FPGA") (pin "P137") (pinfunction "IO_L04N_0_P137") (pintype "bidirectional"))
      (node (ref "SDRAM") (pin "35") (pinfunction "A11_35") (pintype "bidirectional"))
    )
    (net (code "84") (name "/SDR_A12") (class "Default")
      (node (ref "FPGA") (pin "P138") (pinfunction "IO_L04P_0_P138") (pintype "bidirectional"))
      (node (ref "SDRAM") (pin "36") (pinfunction "A12_36") (pintype "bidirectional"))
    )
    (net (code "85") (name "/SDR_BA0") (class "Default")
      (node (ref "FPGA") (pin "P15") (pinfunction "IO_L44P_GCLK21_3_P15") (pintype "bidirectional"))
      (node (ref "SDRAM") (pin "20") (pinfunction "BA0_20") (pintype "bidirectional"))
    )
    (net (code "86") (name "/SDR_BA1") (class "Default")
      (node (ref "FPGA") (pin "P14") (pinfunction "IO_L44N_GCLK20_3_P14") (pintype "bidirectional"))
      (node (ref "SDRAM") (pin "21") (pinfunction "BA1_21") (pintype "bidirectional"))
    )
    (net (code "87") (name "/SDR_CAS") (class "Default")
      (node (ref "FPGA") (pin "P21") (pinfunction "IO_L42N_GCLK24_3_P21") (pintype "bidirectional"))
      (node (ref "SDRAM") (pin "17") (pinfunction "CAS_17") (pintype "bidirectional"))
    )
    (net (code "88") (name "/SDR_CKE") (class "Default")
      (node (ref "FPGA") (pin "P139") (pinfunction "IO_L03N_0_P139") (pintype "bidirectional"))
      (node (ref "SDRAM") (pin "37") (pinfunction "CKE_37") (pintype "bidirectional"))
    )
    (net (code "89") (name "/SDR_CLK") (class "Default")
      (node (ref "FPGA") (pin "P140") (pinfunction "IO_L03P_0_P140") (pintype "bidirectional"))
      (node (ref "SDRAM") (pin "38") (pinfunction "CLK_38") (pintype "bidirectional"))
    )
    (net (code "90") (name "/SDR_CS") (class "Default")
      (node (ref "FPGA") (pin "P16") (pinfunction "IO_L43N_GCLK22_IRDY2_3_P16") (pintype "bidirectional"))
      (node (ref "SDRAM") (pin "19") (pinfunction "CS_19") (pintype "bidirectional"))
    )
    (net (code "91") (name "/SDR_DQ0") (class "Default")
      (node (ref "FPGA") (pin "P34") (pinfunction "IO_L01N_VREF_3_P34") (pintype "bidirectional"))
      (node (ref "SDRAM") (pin "2") (pinfunction "DQ0_2") (pintype "bidirectional"))
    )
    (net (code "92") (name "/SDR_DQ1") (class "Default")
      (node (ref "FPGA") (pin "P33") (pinfunction "IO_L02P_3_P33") (pintype "bidirectional"))
      (node (ref "SDRAM") (pin "4") (pinfunction "DQ1_4") (pintype "bidirectional"))
    )
    (net (code "93") (name "/SDR_DQ2") (class "Default")
      (node (ref "FPGA") (pin "P32") (pinfunction "IO_L02N_3_P32") (pintype "bidirectional"))
      (node (ref "SDRAM") (pin "5") (pinfunction "DQ2_5") (pintype "bidirectional"))
    )
    (net (code "94") (name "/SDR_DQ3") (class "Default")
      (node (ref "FPGA") (pin "P30") (pinfunction "IO_L36P_3_P30") (pintype "bidirectional"))
      (node (ref "SDRAM") (pin "7") (pinfunction "DQ3_7") (pintype "bidirectional"))
    )
    (net (code "95") (name "/SDR_DQ4") (class "Default")
      (node (ref "FPGA") (pin "P29") (pinfunction "IO_L36N_3_P29") (pintype "bidirectional"))
      (node (ref "SDRAM") (pin "8") (pinfunction "DQ4_8") (pintype "bidirectional"))
    )
    (net (code "96") (name "/SDR_DQ5") (class "Default")
      (node (ref "FPGA") (pin "P27") (pinfunction "IO_L37P_3_P27") (pintype "bidirectional"))
      (node (ref "SDRAM") (pin "10") (pinfunction "DQ5_10") (pintype "bidirectional"))
    )
    (net (code "97") (name "/SDR_DQ6") (class "Default")
      (node (ref "FPGA") (pin "P26") (pinfunction "IO_L37N_3_P26") (pintype "bidirectional"))
      (node (ref "SDRAM") (pin "11") (pinfunction "DQ6_11") (pintype "bidirectional"))
    )
    (net (code "98") (name "/SDR_DQ7") (class "Default")
      (node (ref "FPGA") (pin "P24") (pinfunction "IO_L41P_GCLK27_3_P24") (pintype "bidirectional"))
      (node (ref "SDRAM") (pin "13") (pinfunction "DQ7_13") (pintype "bidirectional"))
    )
    (net (code "99") (name "/SDR_DQ8") (class "Default")
      (node (ref "FPGA") (pin "P142") (pinfunction "IO_L02P_0_P142") (pintype "bidirectional"))
      (node (ref "SDRAM") (pin "42") (pinfunction "DQ8_42") (pintype "bidirectional"))
    )
    (net (code "100") (name "/SDR_DQ9") (class "Default")
      (node (ref "FPGA") (pin "P143") (pinfunction "IO_L01N_VREF_0_P143") (pintype "bidirectional"))
      (node (ref "SDRAM") (pin "44") (pinfunction "DQ9_44") (pintype "bidirectional"))
    )
    (net (code "101") (name "/SDR_DQ10") (class "Default")
      (node (ref "FPGA") (pin "P144") (pinfunction "IO_L01P_HSWAPEN_0_P144") (pintype "bidirectional"))
      (node (ref "SDRAM") (pin "45") (pinfunction "DQ10_45") (pintype "bidirectional"))
    )
    (net (code "102") (name "/SDR_DQ11") (class "Default")
      (node (ref "FPGA") (pin "P1") (pinfunction "IO_L83N_VREF_3_P1") (pintype "bidirectional"))
      (node (ref "SDRAM") (pin "47") (pinfunction "DQ11_47") (pintype "bidirectional"))
    )
    (net (code "103") (name "/SDR_DQ12") (class "Default")
      (node (ref "FPGA") (pin "P2") (pinfunction "IO_L83P_3_P2") (pintype "bidirectional"))
      (node (ref "SDRAM") (pin "48") (pinfunction "DQ12_48") (pintype "bidirectional"))
    )
    (net (code "104") (name "/SDR_DQ13") (class "Default")
      (node (ref "FPGA") (pin "P5") (pinfunction "IO_L52N_3_P5") (pintype "bidirectional"))
      (node (ref "SDRAM") (pin "50") (pinfunction "DQ13_50") (pintype "bidirectional"))
    )
    (net (code "105") (name "/SDR_DQ14") (class "Default")
      (node (ref "FPGA") (pin "P6") (pinfunction "IO_L52P_3_P6") (pintype "bidirectional"))
      (node (ref "SDRAM") (pin "51") (pinfunction "DQ14_51") (pintype "bidirectional"))
    )
    (net (code "106") (name "/SDR_DQ15") (class "Default")
      (node (ref "FPGA") (pin "P7") (pinfunction "IO_L51N_3_P7") (pintype "bidirectional"))
      (node (ref "SDRAM") (pin "53") (pinfunction "DQ15_53") (pintype "bidirectional"))
    )
    (net (code "107") (name "/SDR_DQMH") (class "Default")
      (node (ref "FPGA") (pin "P141") (pinfunction "IO_L02N_0_P141") (pintype "bidirectional"))
      (node (ref "SDRAM") (pin "39") (pinfunction "DQMH_39") (pintype "bidirectional"))
    )
    (net (code "108") (name "/SDR_DQML") (class "Default")
      (node (ref "FPGA") (pin "P23") (pinfunction "IO_L41N_GCLK26_3_P23") (pintype "bidirectional"))
      (node (ref "SDRAM") (pin "15") (pinfunction "DQML_15") (pintype "bidirectional"))
    )
    (net (code "109") (name "/SDR_RAS") (class "Default")
      (node (ref "FPGA") (pin "P17") (pinfunction "IO_L43P_GCLK23_3_P17") (pintype "bidirectional"))
      (node (ref "SDRAM") (pin "18") (pinfunction "RAS_18") (pintype "bidirectional"))
    )
    (net (code "110") (name "/SDR_WE") (class "Default")
      (node (ref "FPGA") (pin "P22") (pinfunction "IO_L42P_GCLK25_TRDY2_3_P22") (pintype "bidirectional"))
      (node (ref "SDRAM") (pin "16") (pinfunction "WE_16") (pintype "bidirectional"))
    )
    (net (code "111") (name "/SD_CLK") (class "Default")
      (node (ref "MCU") (pin "80") (pinfunction "SDIO_CLK_80") (pintype "bidirectional"))
      (node (ref "MICROSD") (pin "5") (pinfunction "SCK_5") (pintype "bidirectional"))
      (node (ref "R38") (pin "2") (pinfunction "2_2") (pintype "passive"))
    )
    (net (code "112") (name "/SD_CMD") (class "Default")
      (node (ref "MCU") (pin "83") (pinfunction "SDIO_CMD_83") (pintype "bidirectional"))
      (node (ref "MICROSD") (pin "3") (pinfunction "DI_3") (pintype "bidirectional"))
      (node (ref "R41") (pin "1") (pinfunction "1_1") (pintype "passive"))
    )
    (net (code "113") (name "/SD_D0") (class "Default")
      (node (ref "MCU") (pin "65") (pinfunction "SDIO_D0_65") (pintype "bidirectional"))
      (node (ref "MICROSD") (pin "7") (pinfunction "DO_7") (pintype "bidirectional"))
      (node (ref "R42") (pin "1") (pinfunction "1_1") (pintype "passive"))
    )
    (net (code "114") (name "/SD_D1") (class "Default")
      (node (ref "MCU") (pin "66") (pinfunction "SDIO_D1_66") (pintype "bidirectional"))
      (node (ref "MICROSD") (pin "8") (pinfunction "RSV_8") (pintype "bidirectional"))
      (node (ref "R43") (pin "1") (pinfunction "1_1") (pintype "passive"))
    )
    (net (code "115") (name "/SD_D2") (class "Default")
      (node (ref "MCU") (pin "78") (pinfunction "SDIO_D2_78") (pintype "bidirectional"))
      (node (ref "MICROSD") (pin "1") (pinfunction "NC_1") (pintype "bidirectional"))
      (node (ref "R39") (pin "1") (pinfunction "1_1") (pintype "passive"))
    )
    (net (code "116") (name "/SD_D3") (class "Default")
      (node (ref "MCU") (pin "79") (pinfunction "SDIO_D3_79") (pintype "bidirectional"))
      (node (ref "MICROSD") (pin "2") (pinfunction "CS_2") (pintype "bidirectional"))
      (node (ref "R40") (pin "1") (pinfunction "1_1") (pintype "passive"))
    )
    (net (code "117") (name "/SD_DETECT") (class "Default")
      (node (ref "MCU") (pin "64") (pinfunction "PC7_64") (pintype "bidirectional"))
      (node (ref "MICROSD") (pin "CD1") (pinfunction "SHIELD_CD1") (pintype "bidirectional"))
      (node (ref "R24") (pin "1") (pinfunction "1_1") (pintype "passive"))
    )
    (net (code "118") (name "/SPI_MISO") (class "Default")
      (node (ref "FPGA") (pin "P67") (pinfunction "IO_L02P_CMPCLK_2_P67") (pintype "bidirectional"))
      (node (ref "MCU") (pin "31") (pinfunction "SPI1_MISO_31") (pintype "bidirectional"))
    )
    (net (code "119") (name "/TCK{slash}SWCLK") (class "Default")
      (node (ref "JTAG") (pin "9") (pinfunction "9_9") (pintype "passive"))
      (node (ref "MCU") (pin "76") (pinfunction "TCK/SWCLK_76") (pintype "bidirectional"))
    )
    (net (code "120") (name "/TDI") (class "Default")
      (node (ref "JTAG") (pin "5") (pinfunction "5_5") (pintype "passive"))
      (node (ref "MCU") (pin "77") (pinfunction "TDI_77") (pintype "bidirectional"))
    )
    (net (code "121") (name "/TDO{slash}SWO") (class "Default")
      (node (ref "JTAG") (pin "13") (pinfunction "13_13") (pintype "passive"))
      (node (ref "MCU") (pin "89") (pinfunction "TDO/SWO_89") (pintype "bidirectional"))
    )
    (net (code "122") (name "/TMDS_CLKN") (class "Default")
      (node (ref "FPGA") (pin "P116") (pinfunction "IO_L64N_SCP4_0_P116") (pintype "bidirectional"))
      (node (ref "R27") (pin "1") (pinfunction "1_1") (pintype "passive"))
      (node (ref "U$2") (pin "P12") (pinfunction "TMDS_CLKN_P12") (pintype "bidirectional"))
    )
    (net (code "123") (name "/TMDS_CLKP") (class "Default")
      (node (ref "FPGA") (pin "P117") (pinfunction "IO_L64P_SCP5_0_P117") (pintype "bidirectional"))
      (node (ref "R27") (pin "2") (pinfunction "1_2") (pintype "passive"))
      (node (ref "U$2") (pin "P10") (pinfunction "TMDS_CLKP_P10") (pintype "bidirectional"))
    )
    (net (code "124") (name "/TMDS_D0N") (class "Default")
      (node (ref "FPGA") (pin "P118") (pinfunction "IO_L63N_SCP6_0_P118") (pintype "bidirectional"))
      (node (ref "R27") (pin "3") (pinfunction "1_3") (pintype "passive"))
      (node (ref "U$2") (pin "P9") (pinfunction "TMDS_D0N_P9") (pintype "bidirectional"))
    )
    (net (code "125") (name "/TMDS_D0P") (class "Default")
      (node (ref "FPGA") (pin "P119") (pinfunction "IO_L63P_SCP7_0_P119") (pintype "bidirectional"))
      (node (ref "R27") (pin "4") (pinfunction "1_4") (pintype "passive"))
      (node (ref "U$2") (pin "P7") (pinfunction "TMDS_D0P_P7") (pintype "bidirectional"))
    )
    (net (code "126") (name "/TMDS_D1N") (class "Default")
      (node (ref "FPGA") (pin "P120") (pinfunction "IO_L62N_VREF_0_P120") (pintype "bidirectional"))
      (node (ref "R28") (pin "1") (pinfunction "1_1") (pintype "passive"))
      (node (ref "U$2") (pin "P6") (pinfunction "TMDS_D1N_P6") (pintype "bidirectional"))
    )
    (net (code "127") (name "/TMDS_D1P") (class "Default")
      (node (ref "FPGA") (pin "P121") (pinfunction "IO_L62P_0_P121") (pintype "bidirectional"))
      (node (ref "R28") (pin "2") (pinfunction "1_2") (pintype "passive"))
      (node (ref "U$2") (pin "P4") (pinfunction "TMDS_D1P_P4") (pintype "bidirectional"))
    )
    (net (code "128") (name "/TMDS_D2N") (class "Default")
      (node (ref "FPGA") (pin "P123") (pinfunction "IO_L37N_GCLK12_0_P123") (pintype "bidirectional"))
      (node (ref "R28") (pin "3") (pinfunction "1_3") (pintype "passive"))
      (node (ref "U$2") (pin "P3") (pinfunction "TMDS_D2N_P3") (pintype "bidirectional"))
    )
    (net (code "129") (name "/TMDS_D2P") (class "Default")
      (node (ref "FPGA") (pin "P124") (pinfunction "IO_L37P_GCLK13_0_P124") (pintype "bidirectional"))
      (node (ref "R28") (pin "4") (pinfunction "1_4") (pintype "passive"))
      (node (ref "U$2") (pin "P1") (pinfunction "TMDS_D2P_P1") (pintype "bidirectional"))
    )
    (net (code "130") (name "/TMS{slash}SWDIO") (class "Default")
      (node (ref "JTAG") (pin "7") (pinfunction "7_7") (pintype "passive"))
      (node (ref "MCU") (pin "72") (pinfunction "TMS/SWDIO_72") (pintype "bidirectional"))
    )
    (net (code "131") (name "/USB_EN") (class "Default")
      (node (ref "MCU") (pin "69") (pinfunction "USB_EN_ID_69") (pintype "bidirectional"))
      (node (ref "MIC5219-5.0YM5") (pin "3") (pinfunction "EN_3") (pintype "input"))
      (node (ref "R25") (pin "1") (pinfunction "1_1") (pintype "passive"))
    )
    (net (code "132") (name "/USB_VBUS") (class "Default")
      (node (ref "C3") (pin "1") (pinfunction "1_1") (pintype "passive"))
      (node (ref "C4") (pin "1") (pinfunction "1_1") (pintype "passive"))
      (node (ref "MCU") (pin "68") (pinfunction "USB_VBUS_68") (pintype "bidirectional"))
      (node (ref "MIC5219-5.0YM5") (pin "5") (pinfunction "OUT_5") (pintype "passive"))
      (node (ref "X1") (pin "VBUS") (pinfunction "VBUS_VBUS") (pintype "bidirectional"))
    )
    (net (code "133") (name "/VSYNC") (class "Default")
      (node (ref "FPGA") (pin "P66") (pinfunction "IO_L02N_CMPMOSI_2_P66") (pintype "bidirectional"))
      (node (ref "MCU") (pin "35") (pinfunction "PB0_35") (pintype "bidirectional"))
    )
    (net (code "134") (name "/{slash}TRST") (class "Default")
      (node (ref "JTAG") (pin "3") (pinfunction "3_3") (pintype "passive"))
      (node (ref "MCU") (pin "90") (pinfunction "TRST_90") (pintype "bidirectional"))
    )
    (net (code "135") (name "GND") (class "Default")
      (node (ref "C1") (pin "1") (pinfunction "1_1") (pintype "passive"))
      (node (ref "C10") (pin "2") (pinfunction "2_2") (pintype "passive"))
      (node (ref "C11") (pin "2") (pinfunction "2_2") (pintype "passive"))
      (node (ref "C12") (pin "2") (pinfunction "2_2") (pintype "passive"))
      (node (ref "C13") (pin "2") (pinfunction "2_2") (pintype "passive"))
      (node (ref "C14") (pin "2") (pinfunction "2_2") (pintype "passive"))
      (node (ref "C15") (pin "2") (pinfunction "2_2") (pintype "passive"))
      (node (ref "C16") (pin "2") (pinfunction "2_2") (pintype "passive"))
      (node (ref "C17") (pin "2") (pinfunction "2_2") (pintype "passive"))
      (node (ref "C18") (pin "2") (pinfunction "2_2") (pintype "passive"))
      (node (ref "C19") (pin "2") (pinfunction "2_2") (pintype "passive"))
      (node (ref "C2") (pin "2") (pinfunction "2_2") (pintype "passive"))
      (node (ref "C20") (pin "1") (pinfunction "1_1") (pintype "passive"))
      (node (ref "C21") (pin "2") (pinfunction "2_2") (pintype "passive"))
      (node (ref "C22") (pin "2") (pinfunction "2_2") (pintype "passive"))
      (node (ref "C23") (pin "2") (pinfunction "2_2") (pintype "passive"))
      (node (ref "C24") (pin "2") (pinfunction "2_2") (pintype "passive"))
      (node (ref "C25") (pin "2") (pinfunction "2_2") (pintype "passive"))
      (node (ref "C26") (pin "2") (pinfunction "2_2") (pintype "passive"))
      (node (ref "C27") (pin "2") (pinfunction "2_2") (pintype "passive"))
      (node (ref "C28") (pin "2") (pinfunction "2_2") (pintype "passive"))
      (node (ref "C29") (pin "2") (pinfunction "2_2") (pintype "passive"))
      (node (ref "C3") (pin "2") (pinfunction "2_2") (pintype "passive"))
      (node (ref "C30") (pin "2") (pinfunction "2_2") (pintype "passive"))
      (node (ref "C31") (pin "2") (pinfunction "2_2") (pintype "passive"))
      (node (ref "C32") (pin "2") (pinfunction "2_2") (pintype "passive"))
      (node (ref "C33") (pin "2") (pinfunction "2_2") (pintype "passive"))
      (node (ref "C34") (pin "2") (pinfunction "2_2") (pintype "passive"))
      (node (ref "C35") (pin "2") (pinfunction "2_2") (pintype "passive"))
      (node (ref "C36") (pin "2") (pinfunction "2_2") (pintype "passive"))
      (node (ref "C37") (pin "2") (pinfunction "2_2") (pintype "passive"))
      (node (ref "C38") (pin "2") (pinfunction "2_2") (pintype "passive"))
      (node (ref "C39") (pin "2") (pinfunction "2_2") (pintype "passive"))
      (node (ref "C4") (pin "2") (pinfunction "2_2") (pintype "passive"))
      (node (ref "C40") (pin "2") (pinfunction "2_2") (pintype "passive"))
      (node (ref "C41") (pin "2") (pinfunction "2_2") (pintype "passive"))
      (node (ref "C42") (pin "2") (pinfunction "2_2") (pintype "passive"))
      (node (ref "C43") (pin "2") (pinfunction "2_2") (pintype "passive"))
      (node (ref "C44") (pin "2") (pinfunction "2_2") (pintype "passive"))
      (node (ref "C45") (pin "2") (pinfunction "-_2") (pintype "passive"))
      (node (ref "C46") (pin "2") (pinfunction "-_2") (pintype "passive"))
      (node (ref "C47") (pin "2") (pinfunction "-_2") (pintype "passive"))
      (node (ref "C48") (pin "2") (pinfunction "-_2") (pintype "passive"))
      (node (ref "C49") (pin "2") (pinfunction "2_2") (pintype "passive"))
      (node (ref "C5") (pin "2") (pinfunction "2_2") (pintype "passive"))
      (node (ref "C6") (pin "2") (pinfunction "2_2") (pintype "passive"))
      (node (ref "C7") (pin "2") (pinfunction "2_2") (pintype "passive"))
      (node (ref "C8") (pin "2") (pinfunction "2_2") (pintype "passive"))
      (node (ref "C9") (pin "2") (pinfunction "2_2") (pintype "passive"))
      (node (ref "ETH_PHY") (pin "15") (pinfunction "AGND1_15") (pintype "bidirectional"))
      (node (ref "ETH_PHY") (pin "19") (pinfunction "AGND2_19") (pintype "bidirectional"))
      (node (ref "ETH_PHY") (pin "35") (pinfunction "IOGND_35") (pintype "bidirectional"))
      (node (ref "ETH_PHY") (pin "36") (pinfunction "DGND_36") (pintype "bidirectional"))
      (node (ref "ETH_PHY") (pin "47") (pinfunction "IOGND2_47") (pintype "bidirectional"))
      (node (ref "FPGA") (pin "P108") (pinfunction "GND_P108") (pintype "power_in"))
      (node (ref "FPGA") (pin "P113") (pinfunction "GND_P113") (pintype "power_in"))
      (node (ref "FPGA") (pin "P13") (pinfunction "GND_P13") (pintype "power_in"))
      (node (ref "FPGA") (pin "P130") (pinfunction "GND_P130") (pintype "power_in"))
      (node (ref "FPGA") (pin "P136") (pinfunction "GND_P136") (pintype "power_in"))
      (node (ref "FPGA") (pin "P25") (pinfunction "GND_P25") (pintype "power_in"))
      (node (ref "FPGA") (pin "P3") (pinfunction "GND_P3") (pintype "power_in"))
      (node (ref "FPGA") (pin "P49") (pinfunction "GND_P49") (pintype "power_in"))
      (node (ref "FPGA") (pin "P54") (pinfunction "GND_P54") (pintype "power_in"))
      (node (ref "FPGA") (pin "P68") (pinfunction "GND_P68") (pintype "power_in"))
      (node (ref "FPGA") (pin "P73") (pinfunction "SUSPEND_P73") (pintype "input"))
      (node (ref "FPGA") (pin "P77") (pinfunction "GND_P77") (pintype "power_in"))
      (node (ref "FPGA") (pin "P91") (pinfunction "GND_P91") (pintype "power_in"))
      (node (ref "FPGA") (pin "P96") (pinfunction "GND_P96") (pintype "power_in"))
      (node (ref "FPGA_JTAG") (pin "11") (pinfunction "11_11") (pintype "passive"))
      (node (ref "FPGA_JTAG") (pin "13") (pinfunction "13_13") (pintype "passive"))
      (node (ref "FPGA_JTAG") (pin "3") (pinfunction "3_3") (pintype "passive"))
      (node (ref "FPGA_JTAG") (pin "5") (pinfunction "5_5") (pintype "passive"))
      (node (ref "FPGA_JTAG") (pin "7") (pinfunction "7_7") (pintype "passive"))
      (node (ref "FPGA_JTAG") (pin "9") (pinfunction "9_9") (pintype "passive"))
      (node (ref "J2") (pin "GND") (pinfunction "GND_GND") (pintype "bidirectional"))
      (node (ref "J2") (pin "GNDBREAK") (pinfunction "GNDBREAK_GNDBREAK") (pintype "bidirectional"))
      (node (ref "JTAG") (pin "10") (pinfunction "10_10") (pintype "passive"))
      (node (ref "JTAG") (pin "12") (pinfunction "12_12") (pintype "passive"))
      (node (ref "JTAG") (pin "14") (pinfunction "14_14") (pintype "passive"))
      (node (ref "JTAG") (pin "16") (pinfunction "16_16") (pintype "passive"))
      (node (ref "JTAG") (pin "18") (pinfunction "18_18") (pintype "passive"))
      (node (ref "JTAG") (pin "20") (pinfunction "20_20") (pintype "passive"))
      (node (ref "JTAG") (pin "4") (pinfunction "4_4") (pintype "passive"))
      (node (ref "JTAG") (pin "6") (pinfunction "6_6") (pintype "passive"))
      (node (ref "JTAG") (pin "8") (pinfunction "8_8") (pintype "passive"))
      (node (ref "LED_L_EYE") (pin "K") (pinfunction "C_K") (pintype "passive"))
      (node (ref "LED_R_EYE") (pin "K") (pinfunction "C_K") (pintype "passive"))
      (node (ref "MCU") (pin "10") (pinfunction "VSS_10") (pintype "bidirectional"))
      (node (ref "MCU") (pin "20") (pinfunction "VSSA_20") (pintype "bidirectional"))
      (node (ref "MCU") (pin "27") (pinfunction "VSS_27") (pintype "bidirectional"))
      (node (ref "MCU") (pin "74") (pinfunction "VSS_74") (pintype "bidirectional"))
      (node (ref "MCU") (pin "99") (pinfunction "VSS_99") (pintype "bidirectional"))
      (node (ref "MIC5219-3.3YM5_1") (pin "2") (pinfunction "GND_2") (pintype "input"))
      (node (ref "MIC5219-3.3YM5_2") (pin "2") (pinfunction "GND_2") (pintype "input"))
      (node (ref "MIC5219-5.0YM1") (pin "2") (pinfunction "GND_2") (pintype "input"))
      (node (ref "MIC5219-5.0YM5") (pin "2") (pinfunction "GND_2") (pintype "input"))
      (node (ref "MICROSD") (pin "6") (pinfunction "GND_6") (pintype "bidirectional"))
      (node (ref "MICROSD") (pin "GND1") (pinfunction "SHIELD_GND1") (pintype "bidirectional"))
      (node (ref "MICROSD") (pin "GND3") (pinfunction "SHIELD_GND3") (pintype "bidirectional"))
      (node (ref "NCP565ST12T3G") (pin "1") (pinfunction "ADJ_1") (pintype "input"))
      (node (ref "OSC_50M") (pin "2") (pinfunction "GND_2") (pintype "bidirectional"))
      (node (ref "R1") (pin "2") (pinfunction "2_2") (pintype "passive"))
      (node (ref "R16") (pin "1") (pinfunction "1_1") (pintype "passive"))
      (node (ref "R18") (pin "1") (pinfunction "1_1") (pintype "passive"))
      (node (ref "R2") (pin "2") (pinfunction "2_2") (pintype "passive"))
      (node (ref "R20") (pin "1") (pinfunction "1_1") (pintype "passive"))
      (node (ref "R3") (pin "2") (pinfunction "2_2") (pintype "passive"))
      (node (ref "R38") (pin "1") (pinfunction "1_1") (pintype "passive"))
      (node (ref "RESET") (pin "1") (pinfunction "1_1") (pintype "passive"))
      (node (ref "RESET") (pin "2") (pinfunction "2_2") (pintype "passive"))
      (node (ref "RJ45") (pin "8") (pinfunction "SHIELD_8") (pintype "bidirectional"))
      (node (ref "SDRAM") (pin "12") (pinfunction "VSSQ2_12") (pintype "bidirectional"))
      (node (ref "SDRAM") (pin "28") (pinfunction "VSS1_28") (pintype "bidirectional"))
      (node (ref "SDRAM") (pin "41") (pinfunction "VSS2_41") (pintype "bidirectional"))
      (node (ref "SDRAM") (pin "46") (pinfunction "VSSQ3_46") (pintype "bidirectional"))
      (node (ref "SDRAM") (pin "52") (pinfunction "VSSQ4_52") (pintype "bidirectional"))
      (node (ref "SDRAM") (pin "54") (pinfunction "VSS3_54") (pintype "bidirectional"))
      (node (ref "SDRAM") (pin "6") (pinfunction "VSSQ1_6") (pintype "bidirectional"))
      (node (ref "U$2") (pin "P11") (pinfunction "TMDS_CLK_SHLD_P11") (pintype "bidirectional"))
      (node (ref "U$2") (pin "P17") (pinfunction "GND_P17") (pintype "bidirectional"))
      (node (ref "U$2") (pin "P2") (pinfunction "TMDS_D2_SHLD_P2") (pintype "bidirectional"))
      (node (ref "U$2") (pin "P5") (pinfunction "TMDS_D1_SHLD_P5") (pintype "bidirectional"))
      (node (ref "U$2") (pin "P8") (pinfunction "TMDS_D0_SHLD_P8") (pintype "bidirectional"))
      (node (ref "U$3") (pin "5") (pinfunction "GND_5") (pintype "bidirectional"))
      (node (ref "U$4") (pin "L") (pinfunction "L_L") (pintype "bidirectional"))
      (node (ref "U$4") (pin "R") (pinfunction "R_R") (pintype "bidirectional"))
      (node (ref "X1") (pin "GND") (pinfunction "GND_GND") (pintype "bidirectional"))
    )
    (net (code "136") (name "Net-(D1-PadA)") (class "Default")
      (node (ref "D1") (pin "A") (pinfunction "A_A") (pintype "passive"))
      (node (ref "J2") (pin "PWR") (pinfunction "PWR_PWR") (pintype "bidirectional"))
    )
    (net (code "137") (name "Net-(ETH_PHY-LED_SPEED{slash}AN1)") (class "Default")
      (node (ref "ETH_PHY") (pin "27") (pinfunction "LED_SPEED/AN1_27") (pintype "bidirectional"))
      (node (ref "R12") (pin "1") (pinfunction "1_1") (pintype "passive"))
    )
    (net (code "138") (name "Net-(ETH_PHY-RBIAS)") (class "Default")
      (node (ref "ETH_PHY") (pin "24") (pinfunction "RBIAS_24") (pintype "bidirectional"))
      (node (ref "R16") (pin "2") (pinfunction "2_2") (pintype "passive"))
    )
    (net (code "139") (name "Net-(ETH_PHY-RD+)") (class "Default")
      (node (ref "ETH_PHY") (pin "14") (pinfunction "RD+_14") (pintype "bidirectional"))
      (node (ref "R10") (pin "1") (pinfunction "1_1") (pintype "passive"))
      (node (ref "RJ45") (pin "1") (pinfunction "RD+_1") (pintype "bidirectional"))
    )
    (net (code "140") (name "Net-(ETH_PHY-RD-)") (class "Default")
      (node (ref "ETH_PHY") (pin "13") (pinfunction "RD-_13") (pintype "bidirectional"))
      (node (ref "R9") (pin "1") (pinfunction "1_1") (pintype "passive"))
      (node (ref "RJ45") (pin "3") (pinfunction "RD-_3") (pintype "bidirectional"))
    )
    (net (code "141") (name "Net-(ETH_PHY-TD+)") (class "Default")
      (node (ref "ETH_PHY") (pin "17") (pinfunction "TD+_17") (pintype "bidirectional"))
      (node (ref "R6") (pin "1") (pinfunction "1_1") (pintype "passive"))
      (node (ref "RJ45") (pin "4") (pinfunction "TD+_4") (pintype "bidirectional"))
    )
    (net (code "142") (name "Net-(ETH_PHY-TD-)") (class "Default")
      (node (ref "ETH_PHY") (pin "16") (pinfunction "TD-_16") (pintype "bidirectional"))
      (node (ref "R5") (pin "1") (pinfunction "1_1") (pintype "passive"))
      (node (ref "RJ45") (pin "6") (pinfunction "TD-_6") (pintype "bidirectional"))
    )
    (net (code "143") (name "Net-(ETH_PHY-TXD_3)") (class "Default")
      (node (ref "ETH_PHY") (pin "6") (pinfunction "TXD_3_6") (pintype "bidirectional"))
      (node (ref "R18") (pin "2") (pinfunction "2_2") (pintype "passive"))
    )
    (net (code "144") (name "Net-(FPGAC-IO_L01P_CCLK_2)") (class "Default")
      (node (ref "FPGA") (pin "P70") (pinfunction "IO_L01P_CCLK_2_P70") (pintype "bidirectional"))
      (node (ref "R29") (pin "1") (pinfunction "1_1") (pintype "passive"))
    )
    (net (code "145") (name "Net-(LED_L_EYE-PadA)") (class "Default")
      (node (ref "LED_L_EYE") (pin "A") (pinfunction "A_A") (pintype "passive"))
      (node (ref "R36") (pin "1") (pinfunction "1_1") (pintype "passive"))
    )
    (net (code "146") (name "Net-(LED_R_EYE-PadA)") (class "Default")
      (node (ref "LED_R_EYE") (pin "A") (pinfunction "A_A") (pintype "passive"))
      (node (ref "R37") (pin "1") (pinfunction "1_1") (pintype "passive"))
    )
    (net (code "147") (name "Net-(MCUE-USB_FS_DM)") (class "Default")
      (node (ref "MCU") (pin "70") (pinfunction "USB_FS_DM_70") (pintype "bidirectional"))
      (node (ref "R22") (pin "2") (pinfunction "2_2") (pintype "passive"))
    )
    (net (code "148") (name "Net-(MCUE-USB_FS_DP)") (class "Default")
      (node (ref "MCU") (pin "71") (pinfunction "USB_FS_DP_71") (pintype "bidirectional"))
      (node (ref "R21") (pin "2") (pinfunction "2_2") (pintype "passive"))
    )
    (net (code "149") (name "Net-(MCUH-OSC_IN)") (class "Default")
      (node (ref "C18") (pin "1") (pinfunction "1_1") (pintype "passive"))
      (node (ref "MCU") (pin "12") (pinfunction "OSC_IN_12") (pintype "bidirectional"))
      (node (ref "Y1") (pin "2") (pinfunction "2_2") (pintype "passive"))
    )
    (net (code "150") (name "Net-(MCUH-OSC_OUT)") (class "Default")
      (node (ref "C19") (pin "1") (pinfunction "1_1") (pintype "passive"))
      (node (ref "MCU") (pin "13") (pinfunction "OSC_OUT_13") (pintype "bidirectional"))
      (node (ref "Y1") (pin "1") (pinfunction "1_1") (pintype "passive"))
    )
    (net (code "151") (name "Net-(MIC5219-3.3YM5_1-BP)") (class "Default")
      (node (ref "C7") (pin "1") (pinfunction "1_1") (pintype "passive"))
      (node (ref "MIC5219-3.3YM5_1") (pin "4") (pinfunction "BP_4") (pintype "input"))
    )
    (net (code "152") (name "Net-(MIC5219-3.3YM5_1-EN)") (class "Default")
      (node (ref "MIC5219-3.3YM5_1") (pin "3") (pinfunction "EN_3") (pintype "input"))
      (node (ref "R7") (pin "1") (pinfunction "1_1") (pintype "passive"))
    )
    (net (code "153") (name "Net-(MIC5219-3.3YM5_2-BP)") (class "Default")
      (node (ref "C11") (pin "1") (pinfunction "1_1") (pintype "passive"))
      (node (ref "MIC5219-3.3YM5_2") (pin "4") (pinfunction "BP_4") (pintype "input"))
    )
    (net (code "154") (name "Net-(MIC5219-3.3YM5_2-EN)") (class "Default")
      (node (ref "MIC5219-3.3YM5_2") (pin "3") (pinfunction "EN_3") (pintype "input"))
      (node (ref "R8") (pin "1") (pinfunction "1_1") (pintype "passive"))
    )
    (net (code "155") (name "Net-(MIC5219-5.0YM1-BP)") (class "Default")
      (node (ref "C28") (pin "1") (pinfunction "1_1") (pintype "passive"))
      (node (ref "MIC5219-5.0YM1") (pin "4") (pinfunction "BP_4") (pintype "input"))
    )
    (net (code "156") (name "Net-(MIC5219-5.0YM1-EN)") (class "Default")
      (node (ref "MIC5219-5.0YM1") (pin "3") (pinfunction "EN_3") (pintype "input"))
      (node (ref "R23") (pin "1") (pinfunction "1_1") (pintype "passive"))
    )
    (net (code "157") (name "Net-(MIC5219-5.0YM5-BP)") (class "Default")
      (node (ref "C2") (pin "1") (pinfunction "1_1") (pintype "passive"))
      (node (ref "MIC5219-5.0YM5") (pin "4") (pinfunction "BP_4") (pintype "input"))
    )
    (net (code "158") (name "Net-(OSC_50M-EN)") (class "Default")
      (node (ref "OSC_50M") (pin "1") (pinfunction "EN_1") (pintype "bidirectional"))
      (node (ref "R26") (pin "1") (pinfunction "1_1") (pintype "passive"))
    )
    (net (code "159") (name "Net-(R21-Pad1)") (class "Default")
      (node (ref "R21") (pin "1") (pinfunction "1_1") (pintype "passive"))
      (node (ref "X1") (pin "D+") (pinfunction "D+_D+") (pintype "bidirectional"))
    )
    (net (code "160") (name "Net-(R22-Pad1)") (class "Default")
      (node (ref "R22") (pin "1") (pinfunction "1_1") (pintype "passive"))
      (node (ref "X1") (pin "D-") (pinfunction "D-_D-") (pintype "bidirectional"))
    )
    (net (code "161") (name "Net-(RJ45-GLED+)") (class "Default")
      (node (ref "R15") (pin "2") (pinfunction "2_2") (pintype "passive"))
      (node (ref "RJ45") (pin "10") (pinfunction "GLED+_10") (pintype "bidirectional"))
    )
    (net (code "162") (name "Net-(RJ45-YLED+)") (class "Default")
      (node (ref "R14") (pin "1") (pinfunction "1_1") (pintype "passive"))
      (node (ref "RJ45") (pin "12") (pinfunction "YLED+_12") (pintype "bidirectional"))
    )
    (net (code "163") (name "Net-(U$2-DETECT)") (class "Default")
      (node (ref "R19") (pin "2") (pinfunction "2_2") (pintype "passive"))
      (node (ref "U$2") (pin "P19") (pinfunction "DETECT_P19") (pintype "bidirectional"))
    )
    (net (code "164") (name "Net-(U$3-SCLA)") (class "Default")
      (node (ref "R32") (pin "1") (pinfunction "1_1") (pintype "passive"))
      (node (ref "U$3") (pin "2") (pinfunction "SCLA_2") (pintype "bidirectional"))
    )
    (net (code "165") (name "Net-(U$3-SDAA)") (class "Default")
      (node (ref "R33") (pin "1") (pinfunction "1_1") (pintype "passive"))
      (node (ref "U$3") (pin "3") (pinfunction "SDAA_3") (pintype "bidirectional"))
    )
    (net (code "166") (name "V+") (class "Default")
      (node (ref "C10") (pin "1") (pinfunction "1_1") (pintype "passive"))
      (node (ref "C14") (pin "1") (pinfunction "1_1") (pintype "passive"))
      (node (ref "C15") (pin "1") (pinfunction "1_1") (pintype "passive"))
      (node (ref "C31") (pin "1") (pinfunction "1_1") (pintype "passive"))
      (node (ref "C47") (pin "1") (pinfunction "+_1") (pintype "passive"))
      (node (ref "C48") (pin "1") (pinfunction "+_1") (pintype "passive"))
      (node (ref "C5") (pin "1") (pinfunction "1_1") (pintype "passive"))
      (node (ref "C6") (pin "1") (pinfunction "1_1") (pintype "passive"))
      (node (ref "D1") (pin "C") (pinfunction "C_C") (pintype "passive"))
      (node (ref "MIC5219-3.3YM5_1") (pin "1") (pinfunction "IN_1") (pintype "input"))
      (node (ref "MIC5219-3.3YM5_2") (pin "1") (pinfunction "IN_1") (pintype "input"))
      (node (ref "MIC5219-5.0YM1") (pin "1") (pinfunction "IN_1") (pintype "input"))
      (node (ref "MIC5219-5.0YM5") (pin "1") (pinfunction "IN_1") (pintype "input"))
      (node (ref "NCP565ST12T3G") (pin "3") (pinfunction "IN_3") (pintype "input"))
      (node (ref "R23") (pin "2") (pinfunction "2_2") (pintype "passive"))
      (node (ref "R25") (pin "2") (pinfunction "2_2") (pintype "passive"))
      (node (ref "R7") (pin "2") (pinfunction "2_2") (pintype "passive"))
      (node (ref "R8") (pin "2") (pinfunction "2_2") (pintype "passive"))
    )
    (net (code "167") (name "VCCINT") (class "Default")
      (node (ref "C16") (pin "1") (pinfunction "1_1") (pintype "passive"))
      (node (ref "C17") (pin "1") (pinfunction "1_1") (pintype "passive"))
      (node (ref "C23") (pin "1") (pinfunction "1_1") (pintype "passive"))
      (node (ref "C32") (pin "1") (pinfunction "1_1") (pintype "passive"))
      (node (ref "C40") (pin "1") (pinfunction "1_1") (pintype "passive"))
      (node (ref "C46") (pin "1") (pinfunction "+_1") (pintype "passive"))
      (node (ref "FPGA") (pin "P128") (pinfunction "VCCINT_P128") (pintype "input"))
      (node (ref "FPGA") (pin "P19") (pinfunction "VCCINT_P19") (pintype "input"))
      (node (ref "FPGA") (pin "P28") (pinfunction "VCCINT_P28") (pintype "input"))
      (node (ref "FPGA") (pin "P52") (pinfunction "VCCINT_P52") (pintype "input"))
      (node (ref "FPGA") (pin "P89") (pinfunction "VCCINT_P89") (pintype "input"))
      (node (ref "NCP565ST12T3G") (pin "2") (pinfunction "OUT_2") (pintype "passive"))
    )
    (net (code "168") (name "VCCIO") (class "Default")
      (node (ref "C12") (pin "1") (pinfunction "1_1") (pintype "passive"))
      (node (ref "C13") (pin "1") (pinfunction "1_1") (pintype "passive"))
      (node (ref "C33") (pin "1") (pinfunction "1_1") (pintype "passive"))
      (node (ref "C34") (pin "1") (pinfunction "1_1") (pintype "passive"))
      (node (ref "C35") (pin "1") (pinfunction "1_1") (pintype "passive"))
      (node (ref "C36") (pin "1") (pinfunction "1_1") (pintype "passive"))
      (node (ref "C37") (pin "1") (pinfunction "1_1") (pintype "passive"))
      (node (ref "C38") (pin "1") (pinfunction "1_1") (pintype "passive"))
      (node (ref "C39") (pin "1") (pinfunction "1_1") (pintype "passive"))
      (node (ref "FPGA") (pin "P103") (pinfunction "VCCO_1_P103") (pintype "input"))
      (node (ref "FPGA") (pin "P122") (pinfunction "VCCO_0_P122") (pintype "input"))
      (node (ref "FPGA") (pin "P125") (pinfunction "VCCO_0_P125") (pintype "input"))
      (node (ref "FPGA") (pin "P129") (pinfunction "VCCAUX_P129") (pintype "input"))
      (node (ref "FPGA") (pin "P135") (pinfunction "VCCO_0_P135") (pintype "input"))
      (node (ref "FPGA") (pin "P18") (pinfunction "VCCO_3_P18") (pintype "input"))
      (node (ref "FPGA") (pin "P20") (pinfunction "VCCAUX_P20") (pintype "input"))
      (node (ref "FPGA") (pin "P31") (pinfunction "VCCO_3_P31") (pintype "input"))
      (node (ref "FPGA") (pin "P36") (pinfunction "VCCAUX_P36") (pintype "input"))
      (node (ref "FPGA") (pin "P4") (pinfunction "VCCO_3_P4") (pintype "input"))
      (node (ref "FPGA") (pin "P42") (pinfunction "VCCO_2_P42") (pintype "input"))
      (node (ref "FPGA") (pin "P53") (pinfunction "VCCAUX_P53") (pintype "input"))
      (node (ref "FPGA") (pin "P63") (pinfunction "VCCO_2_P63") (pintype "input"))
      (node (ref "FPGA") (pin "P76") (pinfunction "VCCO_1_P76") (pintype "input"))
      (node (ref "FPGA") (pin "P86") (pinfunction "VCCO_1_P86") (pintype "input"))
      (node (ref "FPGA") (pin "P90") (pinfunction "VCCAUX_P90") (pintype "input"))
      (node (ref "FPGA_JTAG") (pin "2") (pinfunction "2_2") (pintype "passive"))
      (node (ref "MIC5219-3.3YM5_2") (pin "5") (pinfunction "OUT_5") (pintype "passive"))
      (node (ref "R27") (pin "5") (pinfunction "2_5") (pintype "passive"))
      (node (ref "R27") (pin "6") (pinfunction "2_6") (pintype "passive"))
      (node (ref "R27") (pin "7") (pinfunction "2_7") (pintype "passive"))
      (node (ref "R27") (pin "8") (pinfunction "2_8") (pintype "passive"))
      (node (ref "R28") (pin "5") (pinfunction "2_5") (pintype "passive"))
      (node (ref "R28") (pin "6") (pinfunction "2_6") (pintype "passive"))
      (node (ref "R28") (pin "7") (pinfunction "2_7") (pintype "passive"))
      (node (ref "R28") (pin "8") (pinfunction "2_8") (pintype "passive"))
      (node (ref "R34") (pin "2") (pinfunction "2_2") (pintype "passive"))
      (node (ref "R35") (pin "2") (pinfunction "2_2") (pintype "passive"))
      (node (ref "SDRAM") (pin "1") (pinfunction "VDD1_1") (pintype "bidirectional"))
      (node (ref "SDRAM") (pin "14") (pinfunction "VDD2_14") (pintype "bidirectional"))
      (node (ref "SDRAM") (pin "27") (pinfunction "VDD3_27") (pintype "bidirectional"))
      (node (ref "SDRAM") (pin "3") (pinfunction "VDDQ1_3") (pintype "bidirectional"))
      (node (ref "SDRAM") (pin "43") (pinfunction "VDDQ3_43") (pintype "bidirectional"))
      (node (ref "SDRAM") (pin "49") (pinfunction "VDDQ4_49") (pintype "bidirectional"))
      (node (ref "SDRAM") (pin "9") (pinfunction "VDDQ2_9") (pintype "bidirectional"))
      (node (ref "U$3") (pin "10") (pinfunction "VCCB_10") (pintype "bidirectional"))
    )
    (net (code "169") (name "unconnected-(ETH_PHY-25MHZ_OUT-Pad25)") (class "Default")
      (node (ref "ETH_PHY") (pin "25") (pinfunction "25MHZ_OUT_25") (pintype "bidirectional"))
    )
    (net (code "170") (name "unconnected-(ETH_PHY-COL{slash}PHYAD0-Pad42)") (class "Default")
      (node (ref "ETH_PHY") (pin "42") (pinfunction "COL/PHYAD0_42") (pintype "bidirectional"))
    )
    (net (code "171") (name "unconnected-(ETH_PHY-CRS{slash}CRS_DV{slash}LED_CFG-Pad40)") (class "Default")
      (node (ref "ETH_PHY") (pin "40") (pinfunction "CRS/CRS_DV/LED_CFG_40") (pintype "bidirectional"))
    )
    (net (code "172") (name "unconnected-(ETH_PHY-RESERVED1-Pad8)") (class "Default")
      (node (ref "ETH_PHY") (pin "8") (pinfunction "RESERVED1_8") (pintype "bidirectional"))
    )
    (net (code "173") (name "unconnected-(ETH_PHY-RESERVED2-Pad9)") (class "Default")
      (node (ref "ETH_PHY") (pin "9") (pinfunction "RESERVED2_9") (pintype "bidirectional"))
    )
    (net (code "174") (name "unconnected-(ETH_PHY-RESERVED3-Pad10)") (class "Default")
      (node (ref "ETH_PHY") (pin "10") (pinfunction "RESERVED3_10") (pintype "bidirectional"))
    )
    (net (code "175") (name "unconnected-(ETH_PHY-RESERVED4-Pad11)") (class "Default")
      (node (ref "ETH_PHY") (pin "11") (pinfunction "RESERVED4_11") (pintype "bidirectional"))
    )
    (net (code "176") (name "unconnected-(ETH_PHY-RESERVED5-Pad12)") (class "Default")
      (node (ref "ETH_PHY") (pin "12") (pinfunction "RESERVED5_12") (pintype "bidirectional"))
    )
    (net (code "177") (name "unconnected-(ETH_PHY-RESERVED6-Pad20)") (class "Default")
      (node (ref "ETH_PHY") (pin "20") (pinfunction "RESERVED6_20") (pintype "bidirectional"))
    )
    (net (code "178") (name "unconnected-(ETH_PHY-RESERVED7-Pad21)") (class "Default")
      (node (ref "ETH_PHY") (pin "21") (pinfunction "RESERVED7_21") (pintype "bidirectional"))
    )
    (net (code "179") (name "unconnected-(ETH_PHY-RXD_2{slash}PHYAD2-Pad45)") (class "Default")
      (node (ref "ETH_PHY") (pin "45") (pinfunction "RXD_2/PHYAD2_45") (pintype "bidirectional"))
    )
    (net (code "180") (name "unconnected-(ETH_PHY-RXD_3{slash}PHYAD3-Pad46)") (class "Default")
      (node (ref "ETH_PHY") (pin "46") (pinfunction "RXD_3/PHYAD3_46") (pintype "bidirectional"))
    )
    (net (code "181") (name "unconnected-(ETH_PHY-RX_CLK-Pad38)") (class "Default")
      (node (ref "ETH_PHY") (pin "38") (pinfunction "RX_CLK_38") (pintype "bidirectional"))
    )
    (net (code "182") (name "unconnected-(ETH_PHY-TXD_2-Pad5)") (class "Default")
      (node (ref "ETH_PHY") (pin "5") (pinfunction "TXD_2_5") (pintype "bidirectional"))
    )
    (net (code "183") (name "unconnected-(ETH_PHY-TX_CLK-Pad1)") (class "Default")
      (node (ref "ETH_PHY") (pin "1") (pinfunction "TX_CLK_1") (pintype "bidirectional"))
    )
    (net (code "184") (name "unconnected-(ETH_PHY-X2-Pad33)") (class "Default")
      (node (ref "ETH_PHY") (pin "33") (pinfunction "X2_33") (pintype "bidirectional"))
    )
    (net (code "185") (name "unconnected-(FPGAA-IO_L65P_SCP3_0-PadP115)") (class "Default")
      (node (ref "FPGA") (pin "P115") (pinfunction "IO_L65P_SCP3_0_P115") (pintype "bidirectional"))
    )
    (net (code "186") (name "unconnected-(FPGAB-IO_L01N_VREF_1-PadP104)") (class "Default")
      (node (ref "FPGA") (pin "P104") (pinfunction "IO_L01N_VREF_1_P104") (pintype "bidirectional"))
    )
    (net (code "187") (name "unconnected-(FPGAB-IO_L01P_1-PadP105)") (class "Default")
      (node (ref "FPGA") (pin "P105") (pinfunction "IO_L01P_1_P105") (pintype "bidirectional"))
    )
    (net (code "188") (name "unconnected-(FPGAB-IO_L32N_1-PadP101)") (class "Default")
      (node (ref "FPGA") (pin "P101") (pinfunction "IO_L32N_1_P101") (pintype "bidirectional"))
    )
    (net (code "189") (name "unconnected-(FPGAB-IO_L32P_1-PadP102)") (class "Default")
      (node (ref "FPGA") (pin "P102") (pinfunction "IO_L32P_1_P102") (pintype "bidirectional"))
    )
    (net (code "190") (name "unconnected-(FPGAB-IO_L74N_DOUT_BUSY_1-PadP74)") (class "Default")
      (node (ref "FPGA") (pin "P74") (pinfunction "IO_L74N_DOUT_BUSY_1_P74") (pintype "bidirectional"))
    )
    (net (code "191") (name "unconnected-(FPGAB-IO_L74P_AWAKE_1-PadP75)") (class "Default")
      (node (ref "FPGA") (pin "P75") (pinfunction "IO_L74P_AWAKE_1_P75") (pintype "bidirectional"))
    )
    (net (code "192") (name "unconnected-(FPGAC-CMPCS_B_2-PadP72)") (class "Default")
      (node (ref "FPGA") (pin "P72") (pinfunction "CMPCS_B_2_P72") (pintype "bidirectional"))
    )
    (net (code "193") (name "unconnected-(FPGAC-IO_L01N_M0_CMPMISO_2-PadP69)") (class "Default")
      (node (ref "FPGA") (pin "P69") (pinfunction "IO_L01N_M0_CMPMISO_2_P69") (pintype "bidirectional"))
    )
    (net (code "194") (name "unconnected-(FPGAC-IO_L64N_D9_2-PadP40)") (class "Default")
      (node (ref "FPGA") (pin "P40") (pinfunction "IO_L64N_D9_2_P40") (pintype "bidirectional"))
    )
    (net (code "195") (name "unconnected-(FPGAC-IO_L65N_CSO_B_2-PadP38)") (class "Default")
      (node (ref "FPGA") (pin "P38") (pinfunction "IO_L65N_CSO_B_2_P38") (pintype "bidirectional"))
    )
    (net (code "196") (name "unconnected-(FPGAD-IO_L01P_3-PadP35)") (class "Default")
      (node (ref "FPGA") (pin "P35") (pinfunction "IO_L01P_3_P35") (pintype "bidirectional"))
    )
    (net (code "197") (name "unconnected-(FPGA_JTAG-Pad1)") (class "Default")
      (node (ref "FPGA_JTAG") (pin "1") (pinfunction "1_1") (pintype "passive"))
    )
    (net (code "198") (name "unconnected-(FPGA_JTAG-Pad12)") (class "Default")
      (node (ref "FPGA_JTAG") (pin "12") (pinfunction "12_12") (pintype "passive"))
    )
    (net (code "199") (name "unconnected-(FPGA_JTAG-Pad14)") (class "Default")
      (node (ref "FPGA_JTAG") (pin "14") (pinfunction "14_14") (pintype "passive"))
    )
    (net (code "200") (name "unconnected-(JTAG-Pad2)") (class "Default")
      (node (ref "JTAG") (pin "2") (pinfunction "2_2") (pintype "passive"))
    )
    (net (code "201") (name "unconnected-(MCUA-BOOT0-Pad94)") (class "Default")
      (node (ref "MCU") (pin "94") (pinfunction "BOOT0_94") (pintype "bidirectional"))
    )
    (net (code "202") (name "unconnected-(MCUA-BOOT1-Pad37)") (class "Default")
      (node (ref "MCU") (pin "37") (pinfunction "BOOT1_37") (pintype "bidirectional"))
    )
    (net (code "203") (name "unconnected-(MCUA-VBAT-Pad6)") (class "Default")
      (node (ref "MCU") (pin "6") (pinfunction "VBAT_6") (pintype "bidirectional"))
    )
    (net (code "204") (name "unconnected-(MCUA-VCAP_1-Pad49)") (class "Default")
      (node (ref "MCU") (pin "49") (pinfunction "VCAP_1_49") (pintype "bidirectional"))
    )
    (net (code "205") (name "unconnected-(MCUA-VCAP_2-Pad73)") (class "Default")
      (node (ref "MCU") (pin "73") (pinfunction "VCAP_2_73") (pintype "bidirectional"))
    )
    (net (code "206") (name "unconnected-(MCUA-VDDA-Pad22)") (class "Default")
      (node (ref "MCU") (pin "22") (pinfunction "VDDA_22") (pintype "bidirectional"))
    )
    (net (code "207") (name "unconnected-(MCUA-VREFP-Pad21)") (class "Default")
      (node (ref "MCU") (pin "21") (pinfunction "VREFP_21") (pintype "bidirectional"))
    )
    (net (code "208") (name "unconnected-(MCUA-WKUP-Pad23)") (class "Default")
      (node (ref "MCU") (pin "23") (pinfunction "WKUP_23") (pintype "bidirectional"))
    )
    (net (code "209") (name "unconnected-(MCUG-SPI1_NSS-Pad29)") (class "Default")
      (node (ref "MCU") (pin "29") (pinfunction "SPI1_NSS_29") (pintype "bidirectional"))
    )
    (net (code "210") (name "unconnected-(MCUH-OSC32_IN-Pad8)") (class "Default")
      (node (ref "MCU") (pin "8") (pinfunction "OSC32_IN_8") (pintype "bidirectional"))
    )
    (net (code "211") (name "unconnected-(MCUH-OSC32_OUT-Pad9)") (class "Default")
      (node (ref "MCU") (pin "9") (pinfunction "OSC32_OUT_9") (pintype "bidirectional"))
    )
    (net (code "212") (name "unconnected-(MCUI-PB6-Pad92)") (class "Default")
      (node (ref "MCU") (pin "92") (pinfunction "PB6_92") (pintype "bidirectional"))
    )
    (net (code "213") (name "unconnected-(MCUI-PB8-Pad95)") (class "Default")
      (node (ref "MCU") (pin "95") (pinfunction "PB8_95") (pintype "bidirectional"))
    )
    (net (code "214") (name "unconnected-(MCUI-PB9-Pad96)") (class "Default")
      (node (ref "MCU") (pin "96") (pinfunction "PB9_96") (pintype "bidirectional"))
    )
    (net (code "215") (name "unconnected-(MCUI-PC0-Pad15)") (class "Default")
      (node (ref "MCU") (pin "15") (pinfunction "PC0_15") (pintype "bidirectional"))
    )
    (net (code "216") (name "unconnected-(MCUI-PC2-Pad17)") (class "Default")
      (node (ref "MCU") (pin "17") (pinfunction "PC2_17") (pintype "bidirectional"))
    )
    (net (code "217") (name "unconnected-(MCUI-PC3-Pad18)") (class "Default")
      (node (ref "MCU") (pin "18") (pinfunction "PC3_18") (pintype "bidirectional"))
    )
    (net (code "218") (name "unconnected-(MCUI-PC13-Pad7)") (class "Default")
      (node (ref "MCU") (pin "7") (pinfunction "PC13_7") (pintype "bidirectional"))
    )
    (net (code "219") (name "unconnected-(MICROSD-SHIELD-PadCD2)") (class "Default")
      (node (ref "MICROSD") (pin "CD2") (pinfunction "SHIELD_CD2") (pintype "bidirectional"))
    )
    (net (code "220") (name "unconnected-(SDRAM-NC-Pad40)") (class "Default")
      (node (ref "SDRAM") (pin "40") (pinfunction "NC_40") (pintype "bidirectional"))
    )
    (net (code "221") (name "unconnected-(U$3-EN-Pad6)") (class "Default")
      (node (ref "U$3") (pin "6") (pinfunction "EN_6") (pintype "bidirectional"))
    )
  )
)
